# 01_Raspberry_Hat_7_Schematic.net
KiCad netlist of a schematic drawn in EAGLE
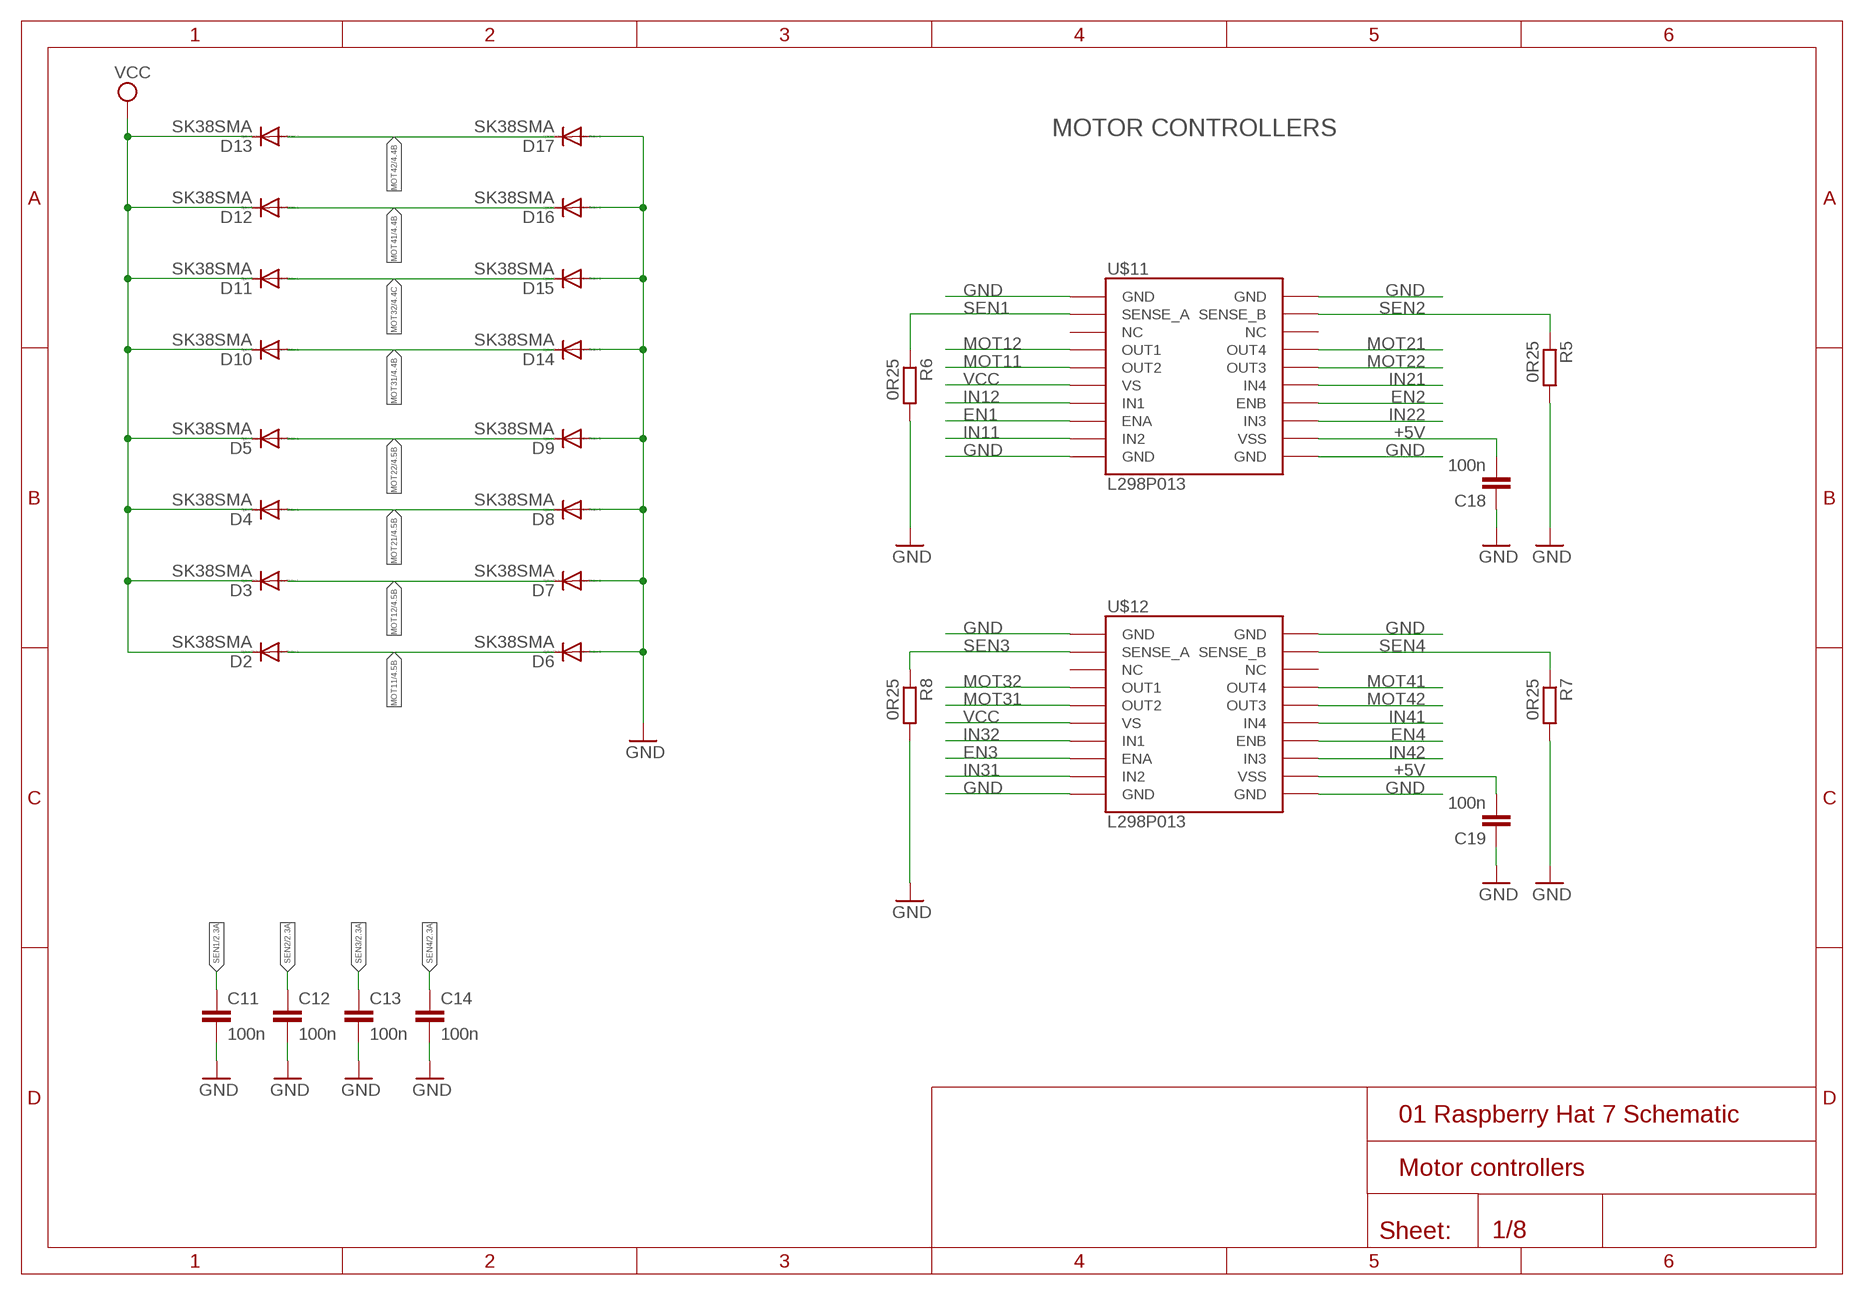
[diagram p0: schematic, sheet 1]
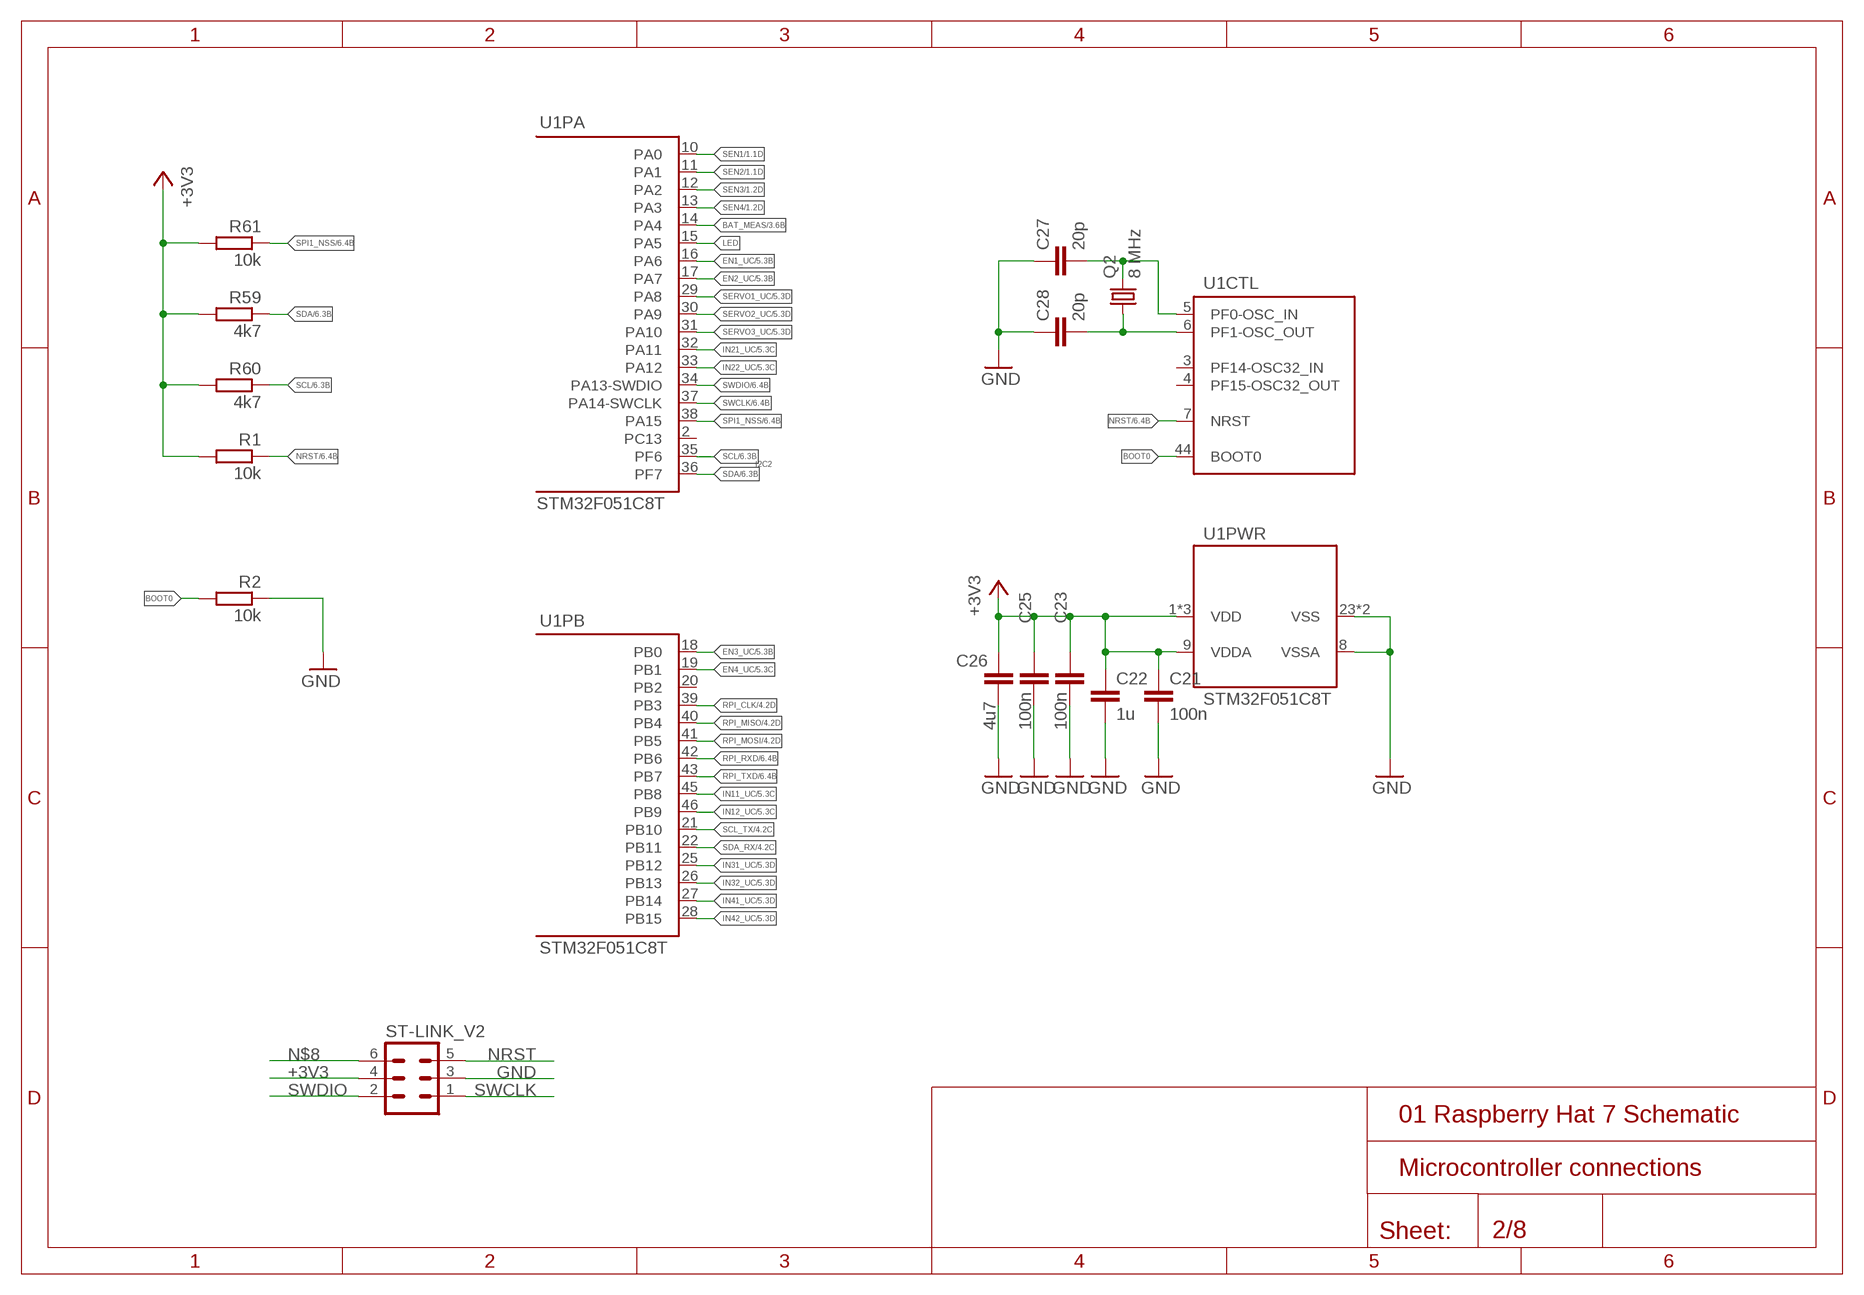
[diagram p1: schematic, sheet 2]
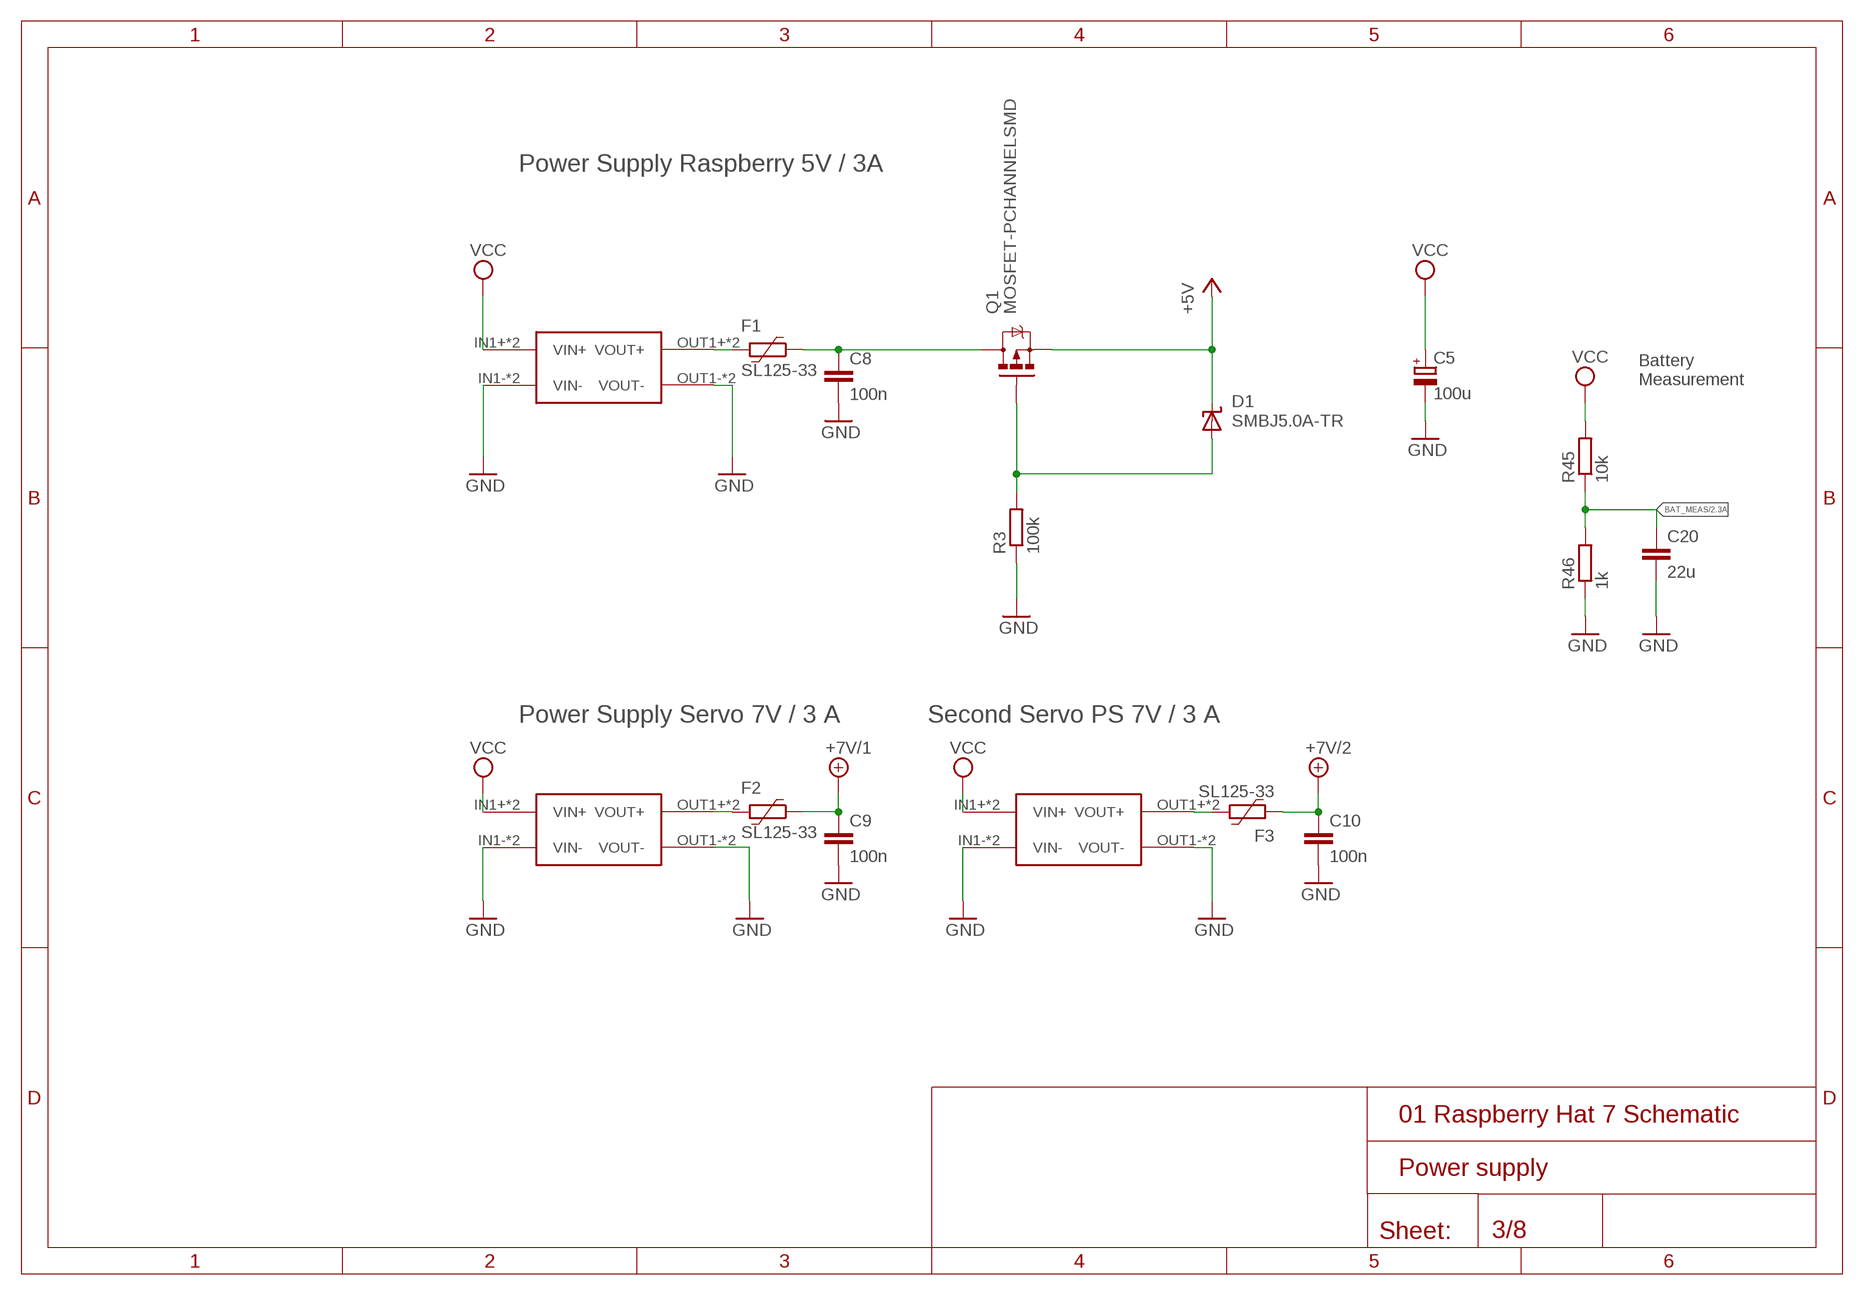
[diagram p2: schematic, sheet 3]
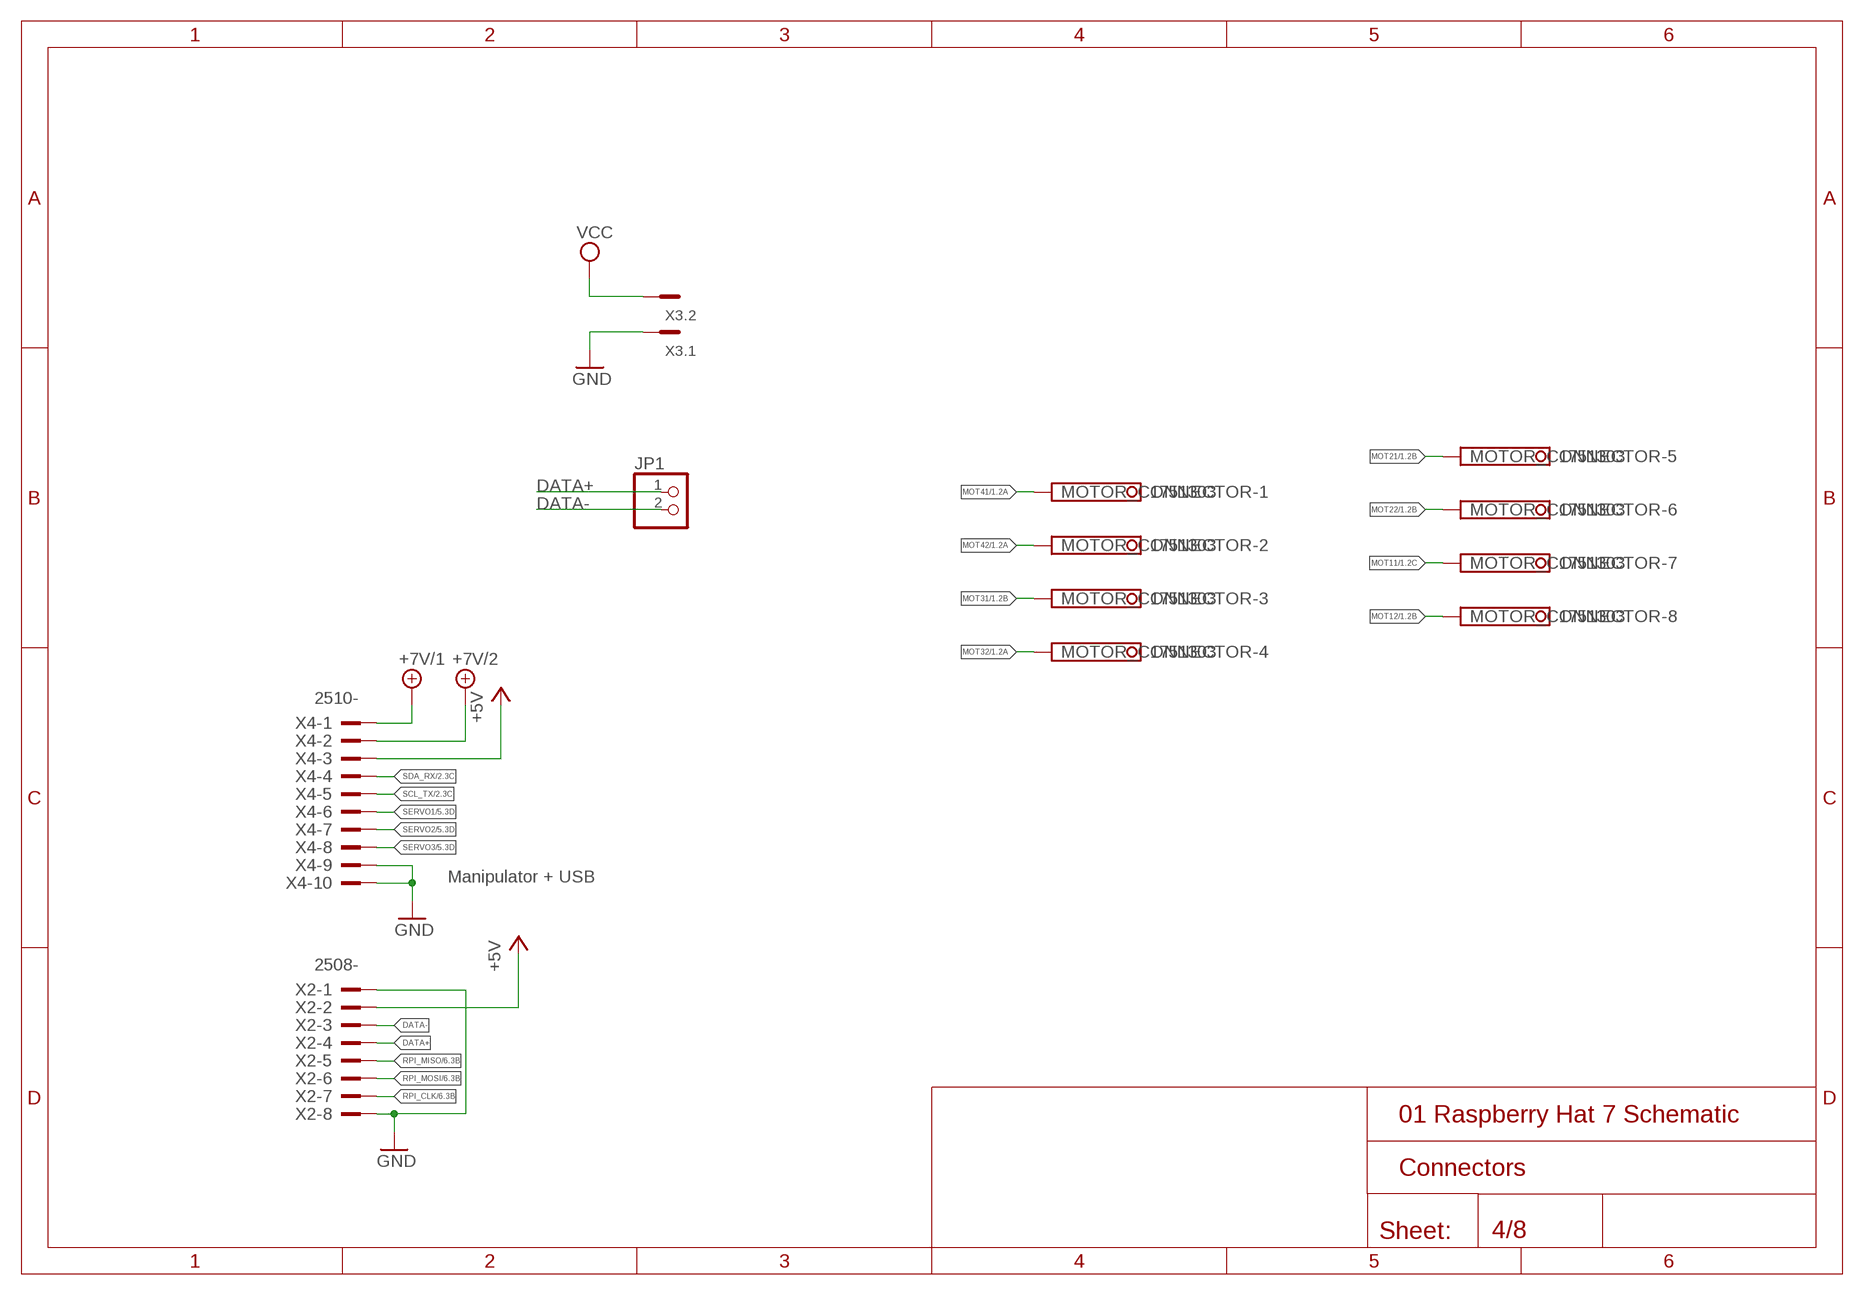
[diagram p3: schematic, sheet 4]
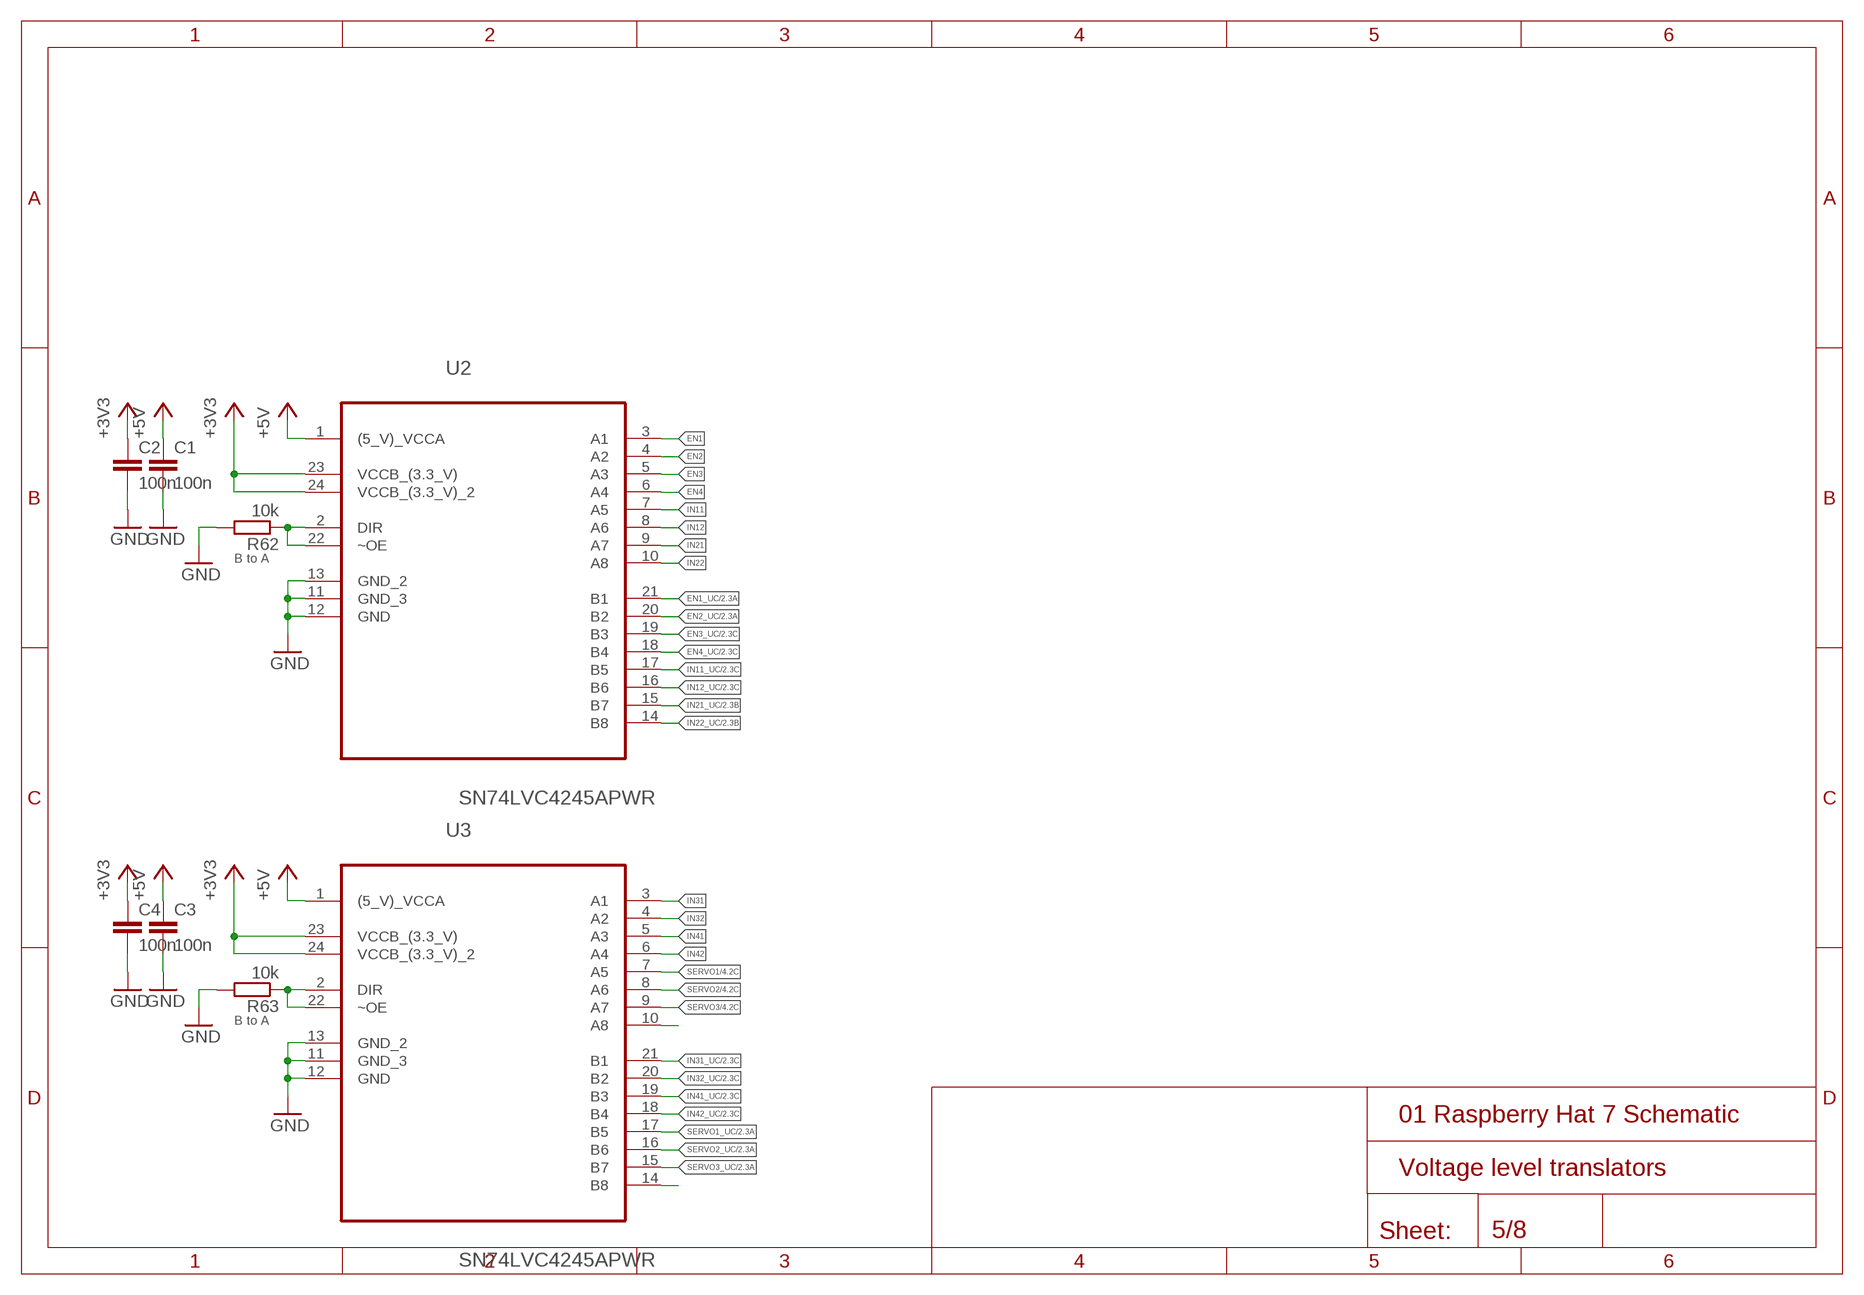
[diagram p4: schematic, sheet 5]
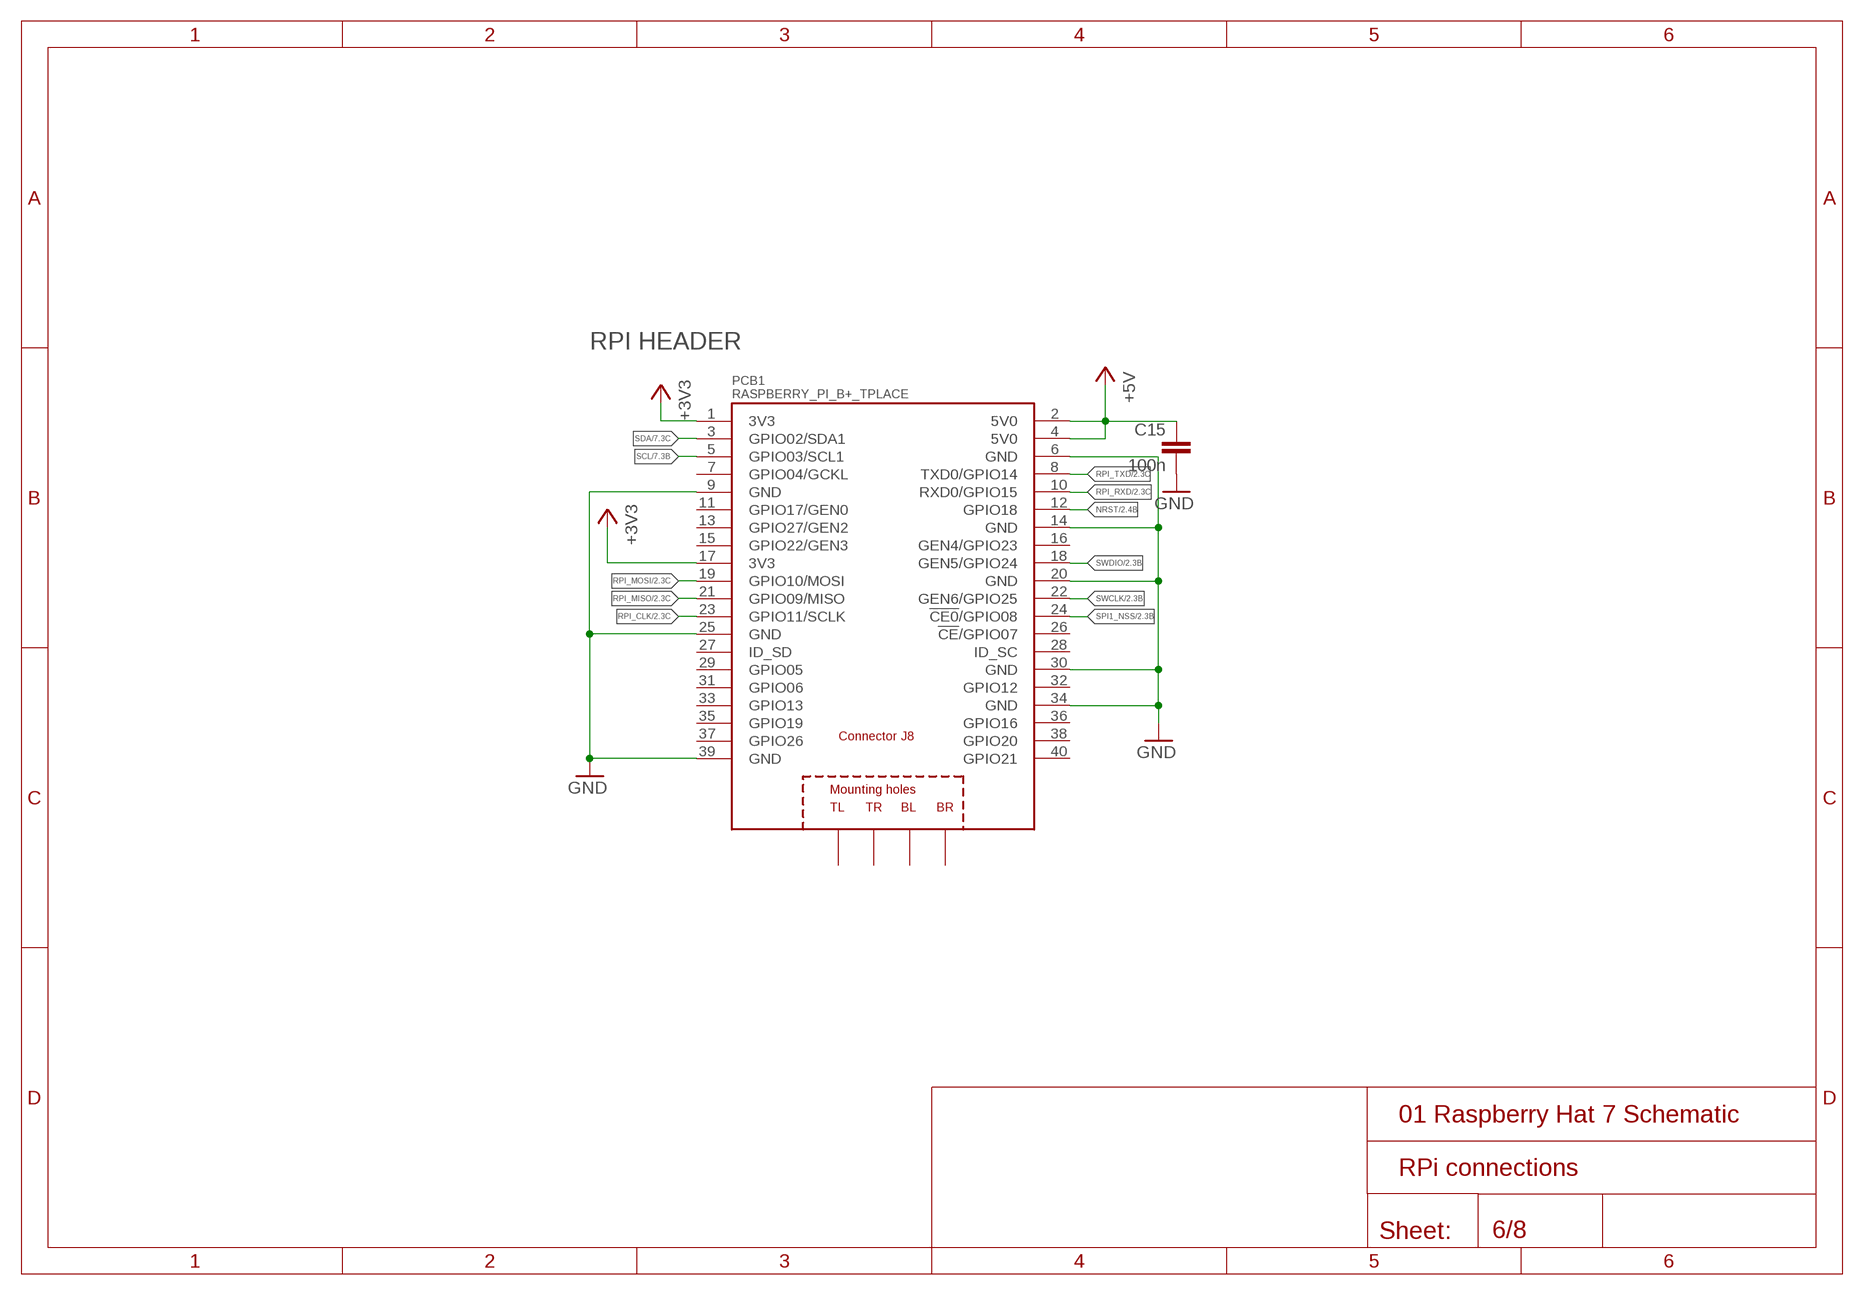
[diagram p5: schematic, sheet 6]
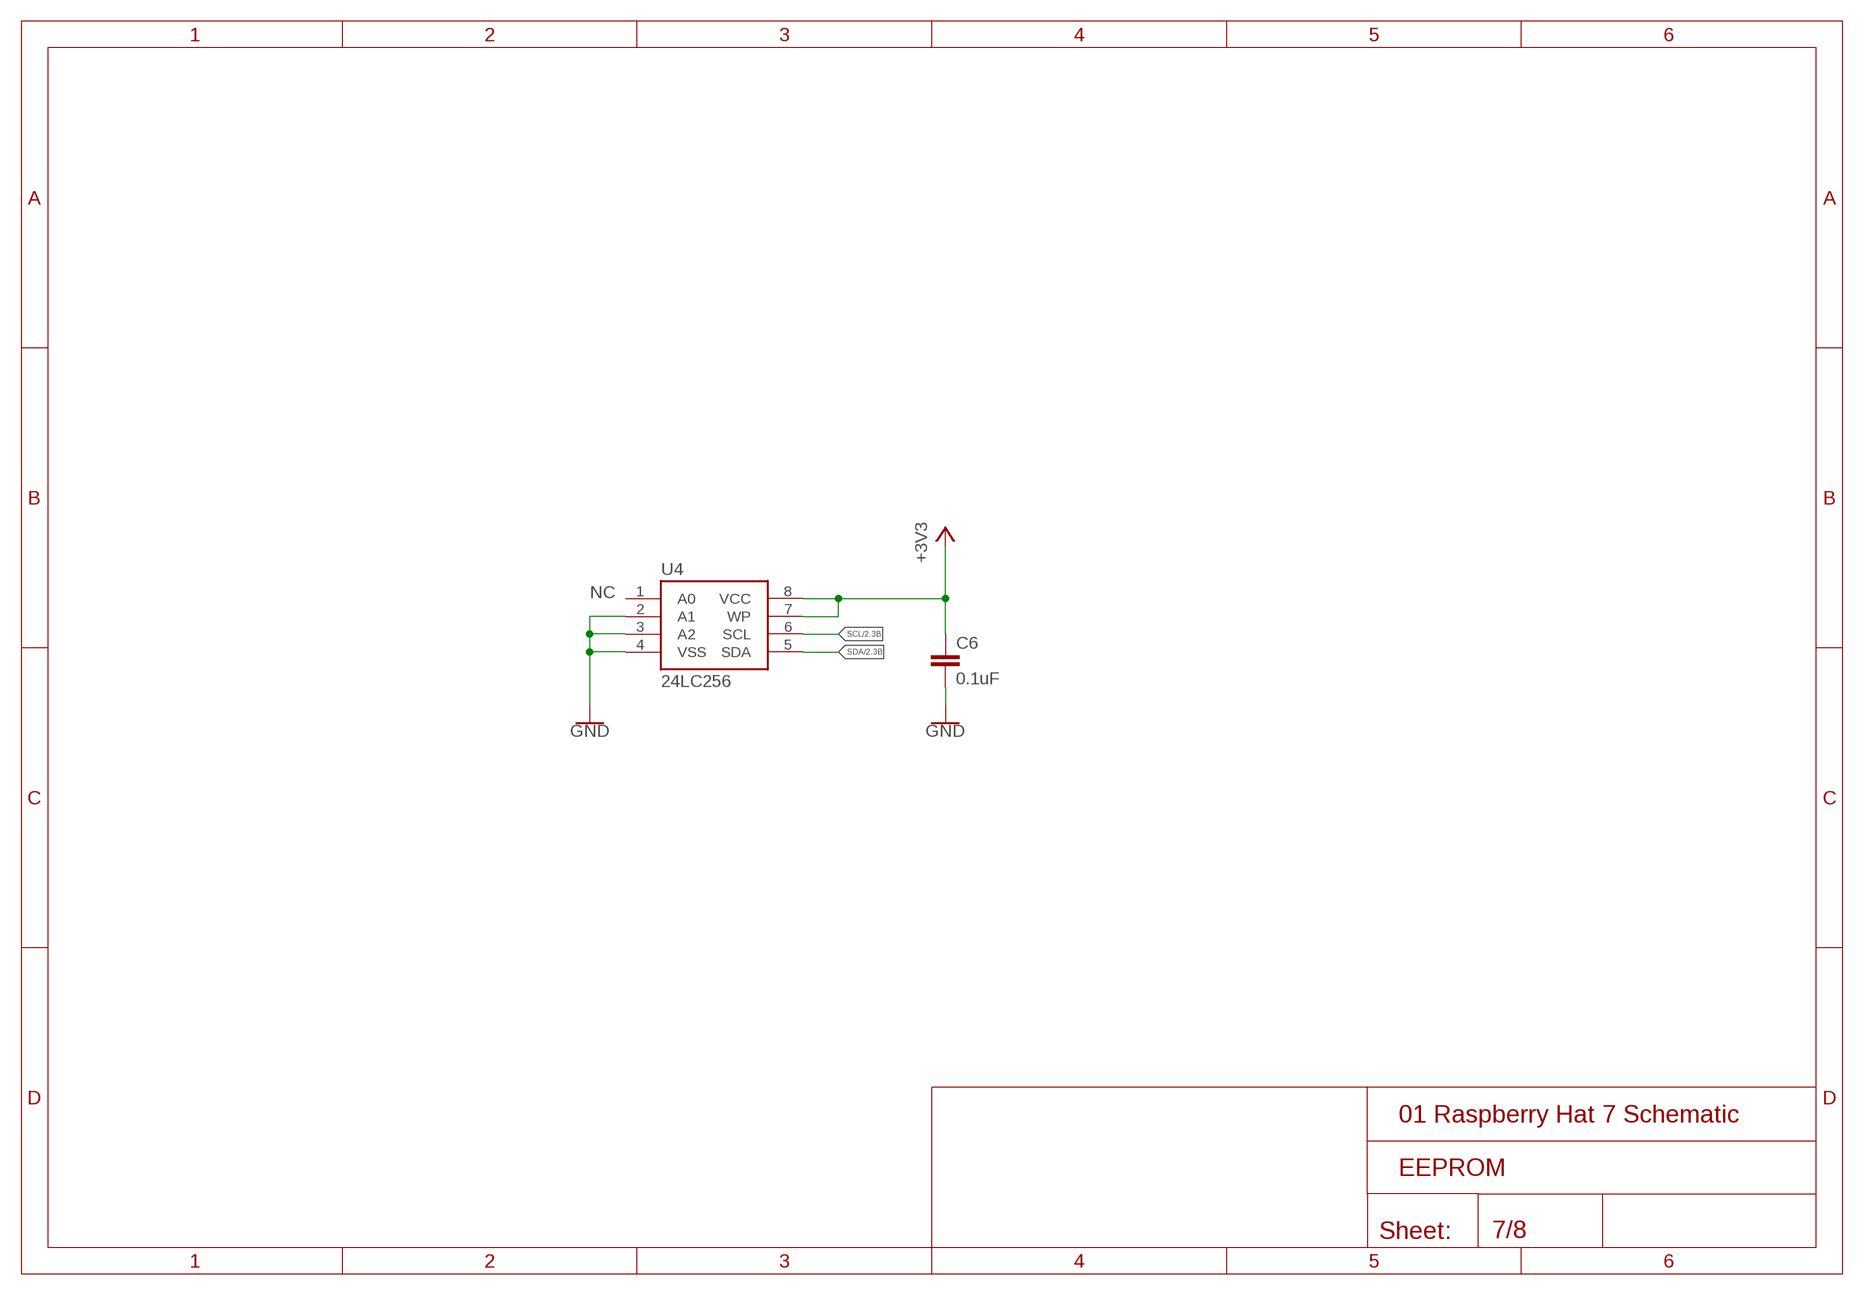
[diagram p6: schematic, sheet 7]
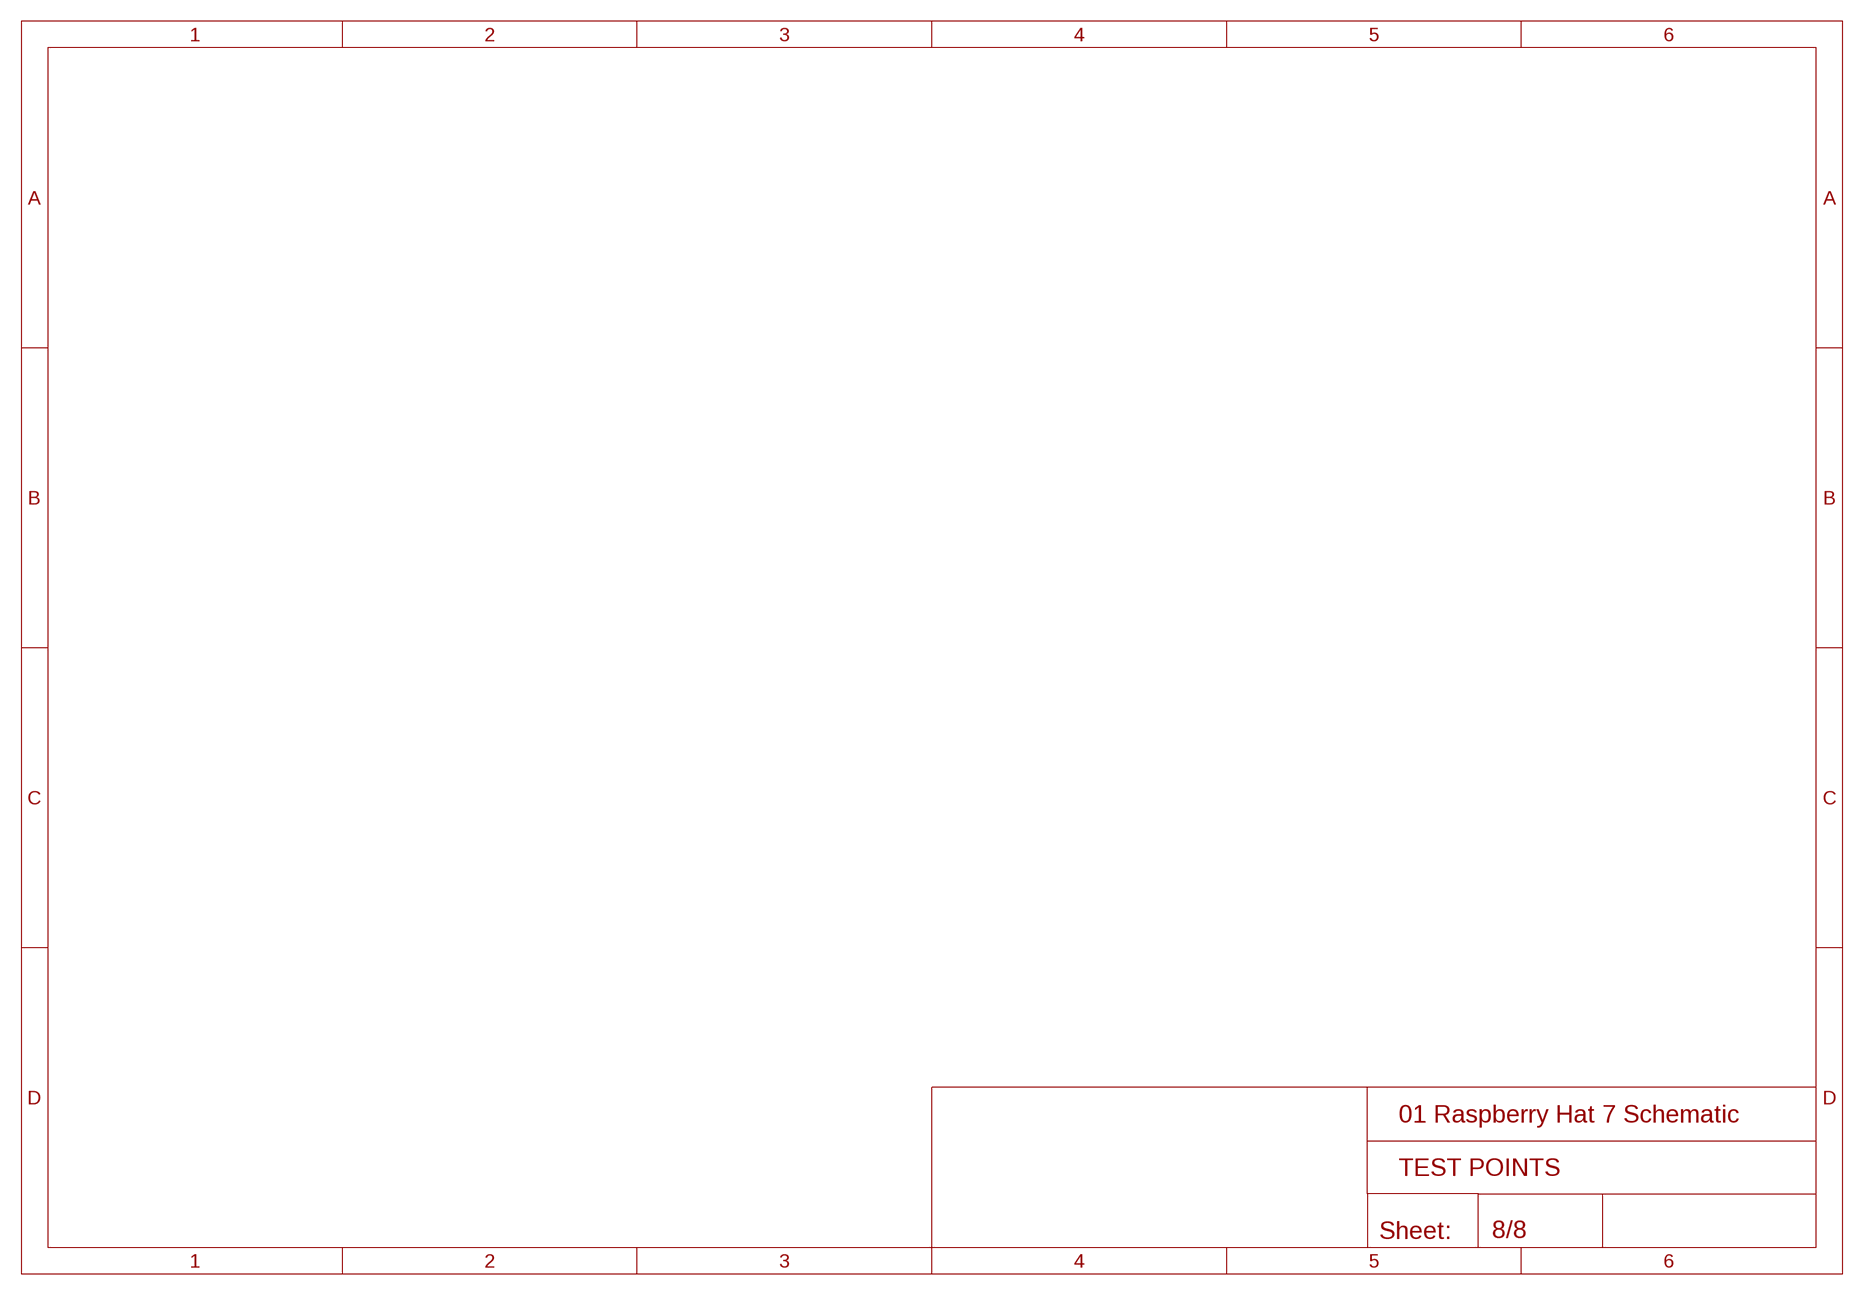
[diagram p7: schematic, sheet 8]

(export (version "E")
  (design (tool "Eeschema 10.0.6"))
  (components
    (comp (ref "C11")
      (value "100n")
      (footprint "eagle-import:C0603K")
      (libsource (lib "eagle-import") (part "resistor_348_C-EUC0603K"))
    )
    (comp (ref "C12")
      (value "100n")
      (footprint "eagle-import:C0603K")
      (libsource (lib "eagle-import") (part "resistor_348_C-EUC0603K"))
    )
    (comp (ref "C13")
      (value "100n")
      (footprint "eagle-import:C0603K")
      (libsource (lib "eagle-import") (part "resistor_348_C-EUC0603K"))
    )
    (comp (ref "C14")
      (value "100n")
      (footprint "eagle-import:C0603K")
      (libsource (lib "eagle-import") (part "resistor_348_C-EUC0603K"))
    )
    (comp (ref "C18")
      (value "100n")
      (footprint "eagle-import:C0603K")
      (libsource (lib "eagle-import") (part "resistor_348_C-EUC0603K"))
    )
    (comp (ref "C19")
      (value "100n")
      (footprint "eagle-import:C0603K")
      (libsource (lib "eagle-import") (part "resistor_348_C-EUC0603K"))
    )
    (comp (ref "D2")
      (value "SK38SMA")
      (footprint "eagle-import:SOD123")
      (libsource (lib "eagle-import") (part "DIODE-SOD123"))
    )
    (comp (ref "D3")
      (value "SK38SMA")
      (footprint "eagle-import:SOD123")
      (libsource (lib "eagle-import") (part "DIODE-SOD123"))
    )
    (comp (ref "D4")
      (value "SK38SMA")
      (footprint "eagle-import:SOD123")
      (libsource (lib "eagle-import") (part "DIODE-SOD123"))
    )
    (comp (ref "D5")
      (value "SK38SMA")
      (footprint "eagle-import:SOD123")
      (libsource (lib "eagle-import") (part "DIODE-SOD123"))
    )
    (comp (ref "D6")
      (value "SK38SMA")
      (footprint "eagle-import:SOD123")
      (libsource (lib "eagle-import") (part "DIODE-SOD123"))
    )
    (comp (ref "D7")
      (value "SK38SMA")
      (footprint "eagle-import:SOD123")
      (libsource (lib "eagle-import") (part "DIODE-SOD123"))
    )
    (comp (ref "D8")
      (value "SK38SMA")
      (footprint "eagle-import:SOD123")
      (libsource (lib "eagle-import") (part "DIODE-SOD123"))
    )
    (comp (ref "D9")
      (value "SK38SMA")
      (footprint "eagle-import:SOD123")
      (libsource (lib "eagle-import") (part "DIODE-SOD123"))
    )
    (comp (ref "D10")
      (value "SK38SMA")
      (footprint "eagle-import:SOD123")
      (libsource (lib "eagle-import") (part "DIODE-SOD123"))
    )
    (comp (ref "D11")
      (value "SK38SMA")
      (footprint "eagle-import:SOD123")
      (libsource (lib "eagle-import") (part "DIODE-SOD123"))
    )
    (comp (ref "D12")
      (value "SK38SMA")
      (footprint "eagle-import:SOD123")
      (libsource (lib "eagle-import") (part "DIODE-SOD123"))
    )
    (comp (ref "D13")
      (value "SK38SMA")
      (footprint "eagle-import:SOD123")
      (libsource (lib "eagle-import") (part "DIODE-SOD123"))
    )
    (comp (ref "D14")
      (value "SK38SMA")
      (footprint "eagle-import:SOD123")
      (libsource (lib "eagle-import") (part "DIODE-SOD123"))
    )
    (comp (ref "D15")
      (value "SK38SMA")
      (footprint "eagle-import:SOD123")
      (libsource (lib "eagle-import") (part "DIODE-SOD123"))
    )
    (comp (ref "D16")
      (value "SK38SMA")
      (footprint "eagle-import:SOD123")
      (libsource (lib "eagle-import") (part "DIODE-SOD123"))
    )
    (comp (ref "D17")
      (value "SK38SMA")
      (footprint "eagle-import:SOD123")
      (libsource (lib "eagle-import") (part "DIODE-SOD123"))
    )
    (comp (ref "R5")
      (value "0R25")
      (footprint "eagle-import:R2512")
      (libsource (lib "eagle-import") (part "R-EU_R2512"))
    )
    (comp (ref "R6")
      (value "0R25")
      (footprint "eagle-import:R2512")
      (libsource (lib "eagle-import") (part "R-EU_R2512"))
    )
    (comp (ref "R7")
      (value "0R25")
      (footprint "eagle-import:R2512")
      (libsource (lib "eagle-import") (part "R-EU_R2512"))
    )
    (comp (ref "R8")
      (value "0R25")
      (footprint "eagle-import:R2512")
      (libsource (lib "eagle-import") (part "R-EU_R2512"))
    )
    (comp (ref "U$11")
      (value "L298P013")
      (footprint "eagle-import:POWERSO20")
      (libsource (lib "eagle-import") (part "L298_BRIDGE_DRIVER"))
    )
    (comp (ref "U$12")
      (value "L298P013")
      (footprint "eagle-import:POWERSO20")
      (libsource (lib "eagle-import") (part "L298_BRIDGE_DRIVER"))
    )
    (comp (ref "C1")
      (value "100n")
      (footprint "eagle-import:C0603K")
      (libsource (lib "eagle-import") (part "resistor_348_C-EUC0603K"))
    )
    (comp (ref "C2")
      (value "100n")
      (footprint "eagle-import:C0603K")
      (libsource (lib "eagle-import") (part "resistor_348_C-EUC0603K"))
    )
    (comp (ref "C3")
      (value "100n")
      (footprint "eagle-import:C0603K")
      (libsource (lib "eagle-import") (part "resistor_348_C-EUC0603K"))
    )
    (comp (ref "C4")
      (value "100n")
      (footprint "eagle-import:C0603K")
      (libsource (lib "eagle-import") (part "resistor_348_C-EUC0603K"))
    )
    (comp (ref "R62")
      (value "10k")
      (footprint "eagle-import:R0603")
      (libsource (lib "eagle-import") (part "resistor_348_R-EU_R0603"))
    )
    (comp (ref "R63")
      (value "10k")
      (footprint "eagle-import:R0603")
      (libsource (lib "eagle-import") (part "resistor_348_R-EU_R0603"))
    )
    (comp (ref "U2")
      (value "SN74LVC4245APWR")
      (footprint "eagle-import:SOP65P640X120-24N")
      (libsource (lib "eagle-import") (part "SN74LVC4245APWR"))
    )
    (comp (ref "U3")
      (value "SN74LVC4245APWR")
      (footprint "eagle-import:SOP65P640X120-24N")
      (libsource (lib "eagle-import") (part "SN74LVC4245APWR"))
    )
    (comp (ref "C21")
      (value "100n")
      (footprint "eagle-import:C0603K")
      (libsource (lib "eagle-import") (part "resistor_348_C-EUC0603K"))
    )
    (comp (ref "C22")
      (value "1u")
      (footprint "eagle-import:C0603K")
      (libsource (lib "eagle-import") (part "resistor_348_C-EUC0603K"))
    )
    (comp (ref "C23")
      (value "100n")
      (footprint "eagle-import:C0603K")
      (libsource (lib "eagle-import") (part "resistor_348_C-EUC0603K"))
    )
    (comp (ref "C25")
      (value "100n")
      (footprint "eagle-import:C0603K")
      (libsource (lib "eagle-import") (part "resistor_348_C-EUC0603K"))
    )
    (comp (ref "C26")
      (value "4u7")
      (footprint "eagle-import:C0603K")
      (libsource (lib "eagle-import") (part "resistor_348_C-EUC0603K"))
    )
    (comp (ref "C27")
      (value "20p")
      (footprint "eagle-import:C0603K")
      (libsource (lib "eagle-import") (part "resistor_348_C-EUC0603K"))
    )
    (comp (ref "C28")
      (value "20p")
      (footprint "eagle-import:C0603K")
      (libsource (lib "eagle-import") (part "resistor_348_C-EUC0603K"))
    )
    (comp (ref "Q2")
      (value "8 MHz")
      (footprint "eagle-import:HC49UP")
      (libsource (lib "eagle-import") (part "CRYSTALHC49UP"))
    )
    (comp (ref "R1")
      (value "10k")
      (footprint "eagle-import:R0603")
      (libsource (lib "eagle-import") (part "resistor_348_R-EU_R0603"))
    )
    (comp (ref "R2")
      (value "10k")
      (footprint "eagle-import:R0603")
      (libsource (lib "eagle-import") (part "resistor_348_R-EU_R0603"))
    )
    (comp (ref "R59")
      (value "4k7")
      (footprint "eagle-import:R0603")
      (libsource (lib "eagle-import") (part "resistor_348_R-EU_R0603"))
    )
    (comp (ref "R60")
      (value "4k7")
      (footprint "eagle-import:R0603")
      (libsource (lib "eagle-import") (part "resistor_348_R-EU_R0603"))
    )
    (comp (ref "R61")
      (value "10k")
      (footprint "eagle-import:R0603")
      (libsource (lib "eagle-import") (part "resistor_348_R-EU_R0603"))
    )
    (comp (ref "ST-LINK_V2")
      (value "ML6")
      (footprint "eagle-import:ML6")
      (libsource (lib "eagle-import") (part "ML6"))
    )
    (comp (ref "U1")
      (value "STM32F051C8T")
      (footprint "eagle-import:LQFP48")
      (libsource (lib "eagle-import") (part "STM32F051CT8"))
    )
    (comp (ref "C15")
      (value "100n")
      (footprint "eagle-import:C0603K")
      (libsource (lib "eagle-import") (part "resistor_348_C-EUC0603K"))
    )
    (comp (ref "PCB1")
      (value "RASPBERRY_PI_B+_TPLACE")
      (footprint "eagle-import:RASPBERRY_PI_BPLUS_TPLACE")
      (libsource (lib "eagle-import") (part "RASPBERRY_PI_B+_TPLACE"))
    )
    (comp (ref "JP1")
      (value "PINHD-1X2")
      (footprint "eagle-import:1X02")
      (libsource (lib "eagle-import") (part "PINHD-1X2"))
    )
    (comp (ref "MOTOR_CONNECTOR")
      (value "1751303")
      (footprint "eagle-import:1751303")
      (libsource (lib "eagle-import") (part "1751303"))
    )
    (comp (ref "X2")
      (value "2508-")
      (footprint "eagle-import:PAK100_2500-10")
      (fields (field (name "MF") "3M") (field (name "MPN") "2510-6002UB"))
      (libsource (lib "eagle-import") (part "2508-"))
    )
    (comp (ref "X3")
      (value "MC2")
      (footprint "eagle-import:MC2")
      (libsource (lib "eagle-import") (part "MC2"))
    )
    (comp (ref "X4")
      (value "2510-")
      (footprint "eagle-import:PAK100_2500-10")
      (fields (field (name "MF") "3M") (field (name "MPN") "2510-6002UB"))
      (libsource (lib "eagle-import") (part "2510-"))
    )
    (comp (ref "C5")
      (value "100u")
      (footprint "eagle-import:153CLV-0807")
      (libsource (lib "eagle-import") (part "CPOL-EU153CLV-0807"))
    )
    (comp (ref "C8")
      (value "100n")
      (footprint "eagle-import:C0603K")
      (libsource (lib "eagle-import") (part "resistor_348_C-EUC0603K"))
    )
    (comp (ref "C9")
      (value "100n")
      (footprint "eagle-import:C0603K")
      (libsource (lib "eagle-import") (part "resistor_348_C-EUC0603K"))
    )
    (comp (ref "C10")
      (value "100n")
      (footprint "eagle-import:C0603K")
      (libsource (lib "eagle-import") (part "resistor_348_C-EUC0603K"))
    )
    (comp (ref "C20")
      (value "22u")
      (footprint "eagle-import:C0603K")
      (libsource (lib "eagle-import") (part "resistor_348_C-EUC0603K"))
    )
    (comp (ref "D1")
      (value "SMBJ5.0A-TR")
      (footprint "eagle-import:SMBJ")
      (libsource (lib "eagle-import") (part "SUPPRESSOR-SMBJ"))
    )
    (comp (ref "F1")
      (value "SL125-33")
      (footprint "eagle-import:2920L")
      (fields (field (name "MF") "Littelfuse") (field (name "MPN") "2920L050"))
      (libsource (lib "eagle-import") (part "?2920L050"))
    )
    (comp (ref "F2")
      (value "SL125-33")
      (footprint "eagle-import:2920L")
      (fields (field (name "MF") "Littelfuse") (field (name "MPN") "2920L050"))
      (libsource (lib "eagle-import") (part "?2920L050"))
    )
    (comp (ref "F3")
      (value "SL125-33")
      (footprint "eagle-import:2920L")
      (fields (field (name "MF") "Littelfuse") (field (name "MPN") "2920L050"))
      (libsource (lib "eagle-import") (part "?2920L050"))
    )
    (comp (ref "Q1")
      (value "MOSFET-PCHANNELSMD")
      (footprint "eagle-import:SOT23-3")
      (libsource (lib "eagle-import") (part "MOSFET-PCHANNELSMD"))
    )
    (comp (ref "R3")
      (value "100k")
      (footprint "eagle-import:R0603")
      (libsource (lib "eagle-import") (part "R-EU_R0603"))
    )
    (comp (ref "R45")
      (value "10k")
      (footprint "eagle-import:R0603")
      (libsource (lib "eagle-import") (part "resistor_348_R-EU_R0603"))
    )
    (comp (ref "R46")
      (value "1k")
      (footprint "eagle-import:R0603")
      (libsource (lib "eagle-import") (part "resistor_348_R-EU_R0603"))
    )
    (comp (ref "U$1")
      (value "MP1584")
      (footprint "eagle-import:DC-BRICK")
      (libsource (lib "eagle-import") (part "MP1584"))
    )
    (comp (ref "U$2")
      (value "MP1584")
      (footprint "eagle-import:DC-BRICK")
      (libsource (lib "eagle-import") (part "MP1584"))
    )
    (comp (ref "U$3")
      (value "MP1584")
      (footprint "eagle-import:DC-BRICK")
      (libsource (lib "eagle-import") (part "MP1584"))
    )
    (comp (ref "C6")
      (value "0.1uF")
      (footprint "eagle-import:C0603")
      (libsource (lib "eagle-import") (part "C-EUC0603"))
    )
    (comp (ref "U4")
      (value "24LC256")
      (footprint "eagle-import:SO08")
      (libsource (lib "eagle-import") (part "EEPROM-I2CSMD"))
    )
  )
  (nets
    (net (code "1") (name "+3V3") (class "Default")
      (node (ref "C2") (pin "1") (pinfunction "1_1") (pintype "passive"))
      (node (ref "C21") (pin "1") (pinfunction "1_1") (pintype "passive"))
      (node (ref "C22") (pin "1") (pinfunction "1_1") (pintype "passive"))
      (node (ref "C23") (pin "1") (pinfunction "1_1") (pintype "passive"))
      (node (ref "C25") (pin "1") (pinfunction "1_1") (pintype "passive"))
      (node (ref "C26") (pin "1") (pinfunction "1_1") (pintype "passive"))
      (node (ref "C4") (pin "1") (pinfunction "1_1") (pintype "passive"))
      (node (ref "C6") (pin "1") (pinfunction "1_1") (pintype "passive"))
      (node (ref "PCB1") (pin "1") (pinfunction "3V3_1") (pintype "power_in"))
      (node (ref "PCB1") (pin "17") (pinfunction "3V3_17") (pintype "power_in"))
      (node (ref "R1") (pin "2") (pinfunction "2_2") (pintype "passive"))
      (node (ref "R59") (pin "2") (pinfunction "2_2") (pintype "passive"))
      (node (ref "R60") (pin "2") (pinfunction "2_2") (pintype "passive"))
      (node (ref "R61") (pin "2") (pinfunction "2_2") (pintype "passive"))
      (node (ref "ST-LINK_V2") (pin "4") (pinfunction "4_4") (pintype "passive"))
      (node (ref "U1") (pin "1") (pinfunction "VDD_1") (pintype "power_in"))
      (node (ref "U1") (pin "24") (pinfunction "VDD_24") (pintype "power_in"))
      (node (ref "U1") (pin "48") (pinfunction "VDD_48") (pintype "power_in"))
      (node (ref "U1") (pin "9") (pinfunction "VDDA_9") (pintype "power_in"))
      (node (ref "U2") (pin "23") (pinfunction "VCCB_(3.3_V)_23") (pintype "power_in"))
      (node (ref "U2") (pin "24") (pinfunction "VCCB_(3.3_V)_2_24") (pintype "power_in"))
      (node (ref "U3") (pin "23") (pinfunction "VCCB_(3.3_V)_23") (pintype "power_in"))
      (node (ref "U3") (pin "24") (pinfunction "VCCB_(3.3_V)_2_24") (pintype "power_in"))
      (node (ref "U4") (pin "7") (pinfunction "WP_7") (pintype "bidirectional"))
      (node (ref "U4") (pin "8") (pinfunction "VCC_8") (pintype "power_in"))
    )
    (net (code "2") (name "+5V") (class "Default")
      (node (ref "C1") (pin "1") (pinfunction "1_1") (pintype "passive"))
      (node (ref "C15") (pin "1") (pinfunction "1_1") (pintype "passive"))
      (node (ref "C18") (pin "2") (pinfunction "2_2") (pintype "passive"))
      (node (ref "C19") (pin "2") (pinfunction "2_2") (pintype "passive"))
      (node (ref "C3") (pin "1") (pinfunction "1_1") (pintype "passive"))
      (node (ref "D1") (pin "C") (pinfunction "C_C") (pintype "passive"))
      (node (ref "PCB1") (pin "2") (pinfunction "5V0_2") (pintype "power_in"))
      (node (ref "PCB1") (pin "4") (pinfunction "5V0_4") (pintype "power_in"))
      (node (ref "Q1") (pin "2") (pinfunction "S_2") (pintype "passive"))
      (node (ref "U$11") (pin "12") (pinfunction "VSS_12") (pintype "bidirectional"))
      (node (ref "U$12") (pin "12") (pinfunction "VSS_12") (pintype "bidirectional"))
      (node (ref "U2") (pin "1") (pinfunction "(5_V)_VCCA_1") (pintype "power_in"))
      (node (ref "U3") (pin "1") (pinfunction "(5_V)_VCCA_1") (pintype "power_in"))
      (node (ref "X2") (pin "2") (pinfunction "KL_2") (pintype "passive"))
      (node (ref "X4") (pin "3") (pinfunction "KL_3") (pintype "passive"))
    )
    (net (code "3") (name "+7V{slash}1") (class "Default")
      (node (ref "C9") (pin "1") (pinfunction "1_1") (pintype "passive"))
      (node (ref "F2") (pin "1") (pinfunction "1_1") (pintype "passive"))
      (node (ref "X4") (pin "1") (pinfunction "KL_1") (pintype "passive"))
    )
    (net (code "4") (name "+7V{slash}2") (class "Default")
      (node (ref "C10") (pin "1") (pinfunction "1_1") (pintype "passive"))
      (node (ref "F3") (pin "2") (pinfunction "2_2") (pintype "passive"))
      (node (ref "X4") (pin "2") (pinfunction "KL_2") (pintype "passive"))
    )
    (net (code "5") (name "BAT_MEAS") (class "Default")
      (node (ref "C20") (pin "1") (pinfunction "1_1") (pintype "passive"))
      (node (ref "R45") (pin "1") (pinfunction "1_1") (pintype "passive"))
      (node (ref "R46") (pin "2") (pinfunction "2_2") (pintype "passive"))
      (node (ref "U1") (pin "14") (pinfunction "PA4_14") (pintype "bidirectional"))
    )
    (net (code "6") (name "BOOT0") (class "Default")
      (node (ref "R2") (pin "2") (pinfunction "2_2") (pintype "passive"))
      (node (ref "U1") (pin "44") (pinfunction "BOOT0_44") (pintype "bidirectional"))
    )
    (net (code "7") (name "DATA+") (class "Default")
      (node (ref "JP1") (pin "1") (pinfunction "1_1") (pintype "passive"))
      (node (ref "X2") (pin "4") (pinfunction "KL_4") (pintype "passive"))
    )
    (net (code "8") (name "DATA-") (class "Default")
      (node (ref "JP1") (pin "2") (pinfunction "2_2") (pintype "passive"))
      (node (ref "X2") (pin "3") (pinfunction "KL_3") (pintype "passive"))
    )
    (net (code "9") (name "EN1") (class "Default")
      (node (ref "U$11") (pin "8") (pinfunction "ENA_8") (pintype "bidirectional"))
      (node (ref "U2") (pin "3") (pinfunction "A1_3") (pintype "output"))
    )
    (net (code "10") (name "EN1_UC") (class "Default")
      (node (ref "U1") (pin "16") (pinfunction "PA6_16") (pintype "bidirectional"))
      (node (ref "U2") (pin "21") (pinfunction "B1_21") (pintype "output"))
    )
    (net (code "11") (name "EN2") (class "Default")
      (node (ref "U$11") (pin "14") (pinfunction "ENB_14") (pintype "bidirectional"))
      (node (ref "U2") (pin "4") (pinfunction "A2_4") (pintype "output"))
    )
    (net (code "12") (name "EN2_UC") (class "Default")
      (node (ref "U1") (pin "17") (pinfunction "PA7_17") (pintype "bidirectional"))
      (node (ref "U2") (pin "20") (pinfunction "B2_20") (pintype "output"))
    )
    (net (code "13") (name "EN3") (class "Default")
      (node (ref "U$12") (pin "8") (pinfunction "ENA_8") (pintype "bidirectional"))
      (node (ref "U2") (pin "5") (pinfunction "A3_5") (pintype "output"))
    )
    (net (code "14") (name "EN3_UC") (class "Default")
      (node (ref "U1") (pin "18") (pinfunction "PB0_18") (pintype "bidirectional"))
      (node (ref "U2") (pin "19") (pinfunction "B3_19") (pintype "output"))
    )
    (net (code "15") (name "EN4") (class "Default")
      (node (ref "U$12") (pin "14") (pinfunction "ENB_14") (pintype "bidirectional"))
      (node (ref "U2") (pin "6") (pinfunction "A4_6") (pintype "output"))
    )
    (net (code "16") (name "EN4_UC") (class "Default")
      (node (ref "U1") (pin "19") (pinfunction "PB1_19") (pintype "bidirectional"))
      (node (ref "U2") (pin "18") (pinfunction "B4_18") (pintype "output"))
    )
    (net (code "17") (name "GND") (class "Default")
      (node (ref "C1") (pin "2") (pinfunction "2_2") (pintype "passive"))
      (node (ref "C10") (pin "2") (pinfunction "2_2") (pintype "passive"))
      (node (ref "C11") (pin "2") (pinfunction "2_2") (pintype "passive"))
      (node (ref "C12") (pin "2") (pinfunction "2_2") (pintype "passive"))
      (node (ref "C13") (pin "2") (pinfunction "2_2") (pintype "passive"))
      (node (ref "C14") (pin "2") (pinfunction "2_2") (pintype "passive"))
      (node (ref "C15") (pin "2") (pinfunction "2_2") (pintype "passive"))
      (node (ref "C18") (pin "1") (pinfunction "1_1") (pintype "passive"))
      (node (ref "C19") (pin "1") (pinfunction "1_1") (pintype "passive"))
      (node (ref "C2") (pin "2") (pinfunction "2_2") (pintype "passive"))
      (node (ref "C20") (pin "2") (pinfunction "2_2") (pintype "passive"))
      (node (ref "C21") (pin "2") (pinfunction "2_2") (pintype "passive"))
      (node (ref "C22") (pin "2") (pinfunction "2_2") (pintype "passive"))
      (node (ref "C23") (pin "2") (pinfunction "2_2") (pintype "passive"))
      (node (ref "C25") (pin "2") (pinfunction "2_2") (pintype "passive"))
      (node (ref "C26") (pin "2") (pinfunction "2_2") (pintype "passive"))
      (node (ref "C27") (pin "1") (pinfunction "1_1") (pintype "passive"))
      (node (ref "C28") (pin "1") (pinfunction "1_1") (pintype "passive"))
      (node (ref "C3") (pin "2") (pinfunction "2_2") (pintype "passive"))
      (node (ref "C4") (pin "2") (pinfunction "2_2") (pintype "passive"))
      (node (ref "C5") (pin "-") (pinfunction "-_-") (pintype "passive"))
      (node (ref "C6") (pin "2") (pinfunction "2_2") (pintype "passive"))
      (node (ref "C8") (pin "2") (pinfunction "2_2") (pintype "passive"))
      (node (ref "C9") (pin "2") (pinfunction "2_2") (pintype "passive"))
      (node (ref "D14") (pin "A") (pinfunction "A_A") (pintype "passive"))
      (node (ref "D15") (pin "A") (pinfunction "A_A") (pintype "passive"))
      (node (ref "D16") (pin "A") (pinfunction "A_A") (pintype "passive"))
      (node (ref "D17") (pin "A") (pinfunction "A_A") (pintype "passive"))
      (node (ref "D6") (pin "A") (pinfunction "A_A") (pintype "passive"))
      (node (ref "D7") (pin "A") (pinfunction "A_A") (pintype "passive"))
      (node (ref "D8") (pin "A") (pinfunction "A_A") (pintype "passive"))
      (node (ref "D9") (pin "A") (pinfunction "A_A") (pintype "passive"))
      (node (ref "PCB1") (pin "14") (pinfunction "GND_14") (pintype "power_in"))
      (node (ref "PCB1") (pin "20") (pinfunction "GND_20") (pintype "power_in"))
      (node (ref "PCB1") (pin "25") (pinfunction "GND_25") (pintype "power_in"))
      (node (ref "PCB1") (pin "30") (pinfunction "GND_30") (pintype "power_in"))
      (node (ref "PCB1") (pin "34") (pinfunction "GND_34") (pintype "power_in"))
      (node (ref "PCB1") (pin "39") (pinfunction "GND_39") (pintype "power_in"))
      (node (ref "PCB1") (pin "6") (pinfunction "GND_6") (pintype "power_in"))
      (node (ref "PCB1") (pin "9") (pinfunction "GND_9") (pintype "power_in"))
      (node (ref "R2") (pin "1") (pinfunction "1_1") (pintype "passive"))
      (node (ref "R3") (pin "1") (pinfunction "1_1") (pintype "passive"))
      (node (ref "R46") (pin "1") (pinfunction "1_1") (pintype "passive"))
      (node (ref "R5") (pin "2") (pinfunction "2_2") (pintype "passive"))
      (node (ref "R6") (pin "2") (pinfunction "2_2") (pintype "passive"))
      (node (ref "R62") (pin "2") (pinfunction "2_2") (pintype "passive"))
      (node (ref "R63") (pin "2") (pinfunction "2_2") (pintype "passive"))
      (node (ref "R7") (pin "2") (pinfunction "2_2") (pintype "passive"))
      (node (ref "R8") (pin "2") (pinfunction "2_2") (pintype "passive"))
      (node (ref "ST-LINK_V2") (pin "3") (pinfunction "3_3") (pintype "passive"))
      (node (ref "U$1") (pin "IN1-") (pinfunction "VIN-_IN1-") (pintype "input"))
      (node (ref "U$1") (pin "IN2-") (pinfunction "VIN-_IN2-") (pintype "input"))
      (node (ref "U$1") (pin "OUT1-") (pinfunction "VOUT-_OUT1-") (pintype "output"))
      (node (ref "U$1") (pin "OUT2-") (pinfunction "VOUT-_OUT2-") (pintype "output"))
      (node (ref "U$11") (pin "1") (pinfunction "GND_1") (pintype "bidirectional"))
      (node (ref "U$11") (pin "10") (pinfunction "GND_10") (pintype "bidirectional"))
      (node (ref "U$11") (pin "11") (pinfunction "GND_11") (pintype "bidirectional"))
      (node (ref "U$11") (pin "20") (pinfunction "GND_20") (pintype "bidirectional"))
      (node (ref "U$12") (pin "1") (pinfunction "GND_1") (pintype "bidirectional"))
      (node (ref "U$12") (pin "10") (pinfunction "GND_10") (pintype "bidirectional"))
      (node (ref "U$12") (pin "11") (pinfunction "GND_11") (pintype "bidirectional"))
      (node (ref "U$12") (pin "20") (pinfunction "GND_20") (pintype "bidirectional"))
      (node (ref "U$2") (pin "IN1-") (pinfunction "VIN-_IN1-") (pintype "input"))
      (node (ref "U$2") (pin "IN2-") (pinfunction "VIN-_IN2-") (pintype "input"))
      (node (ref "U$2") (pin "OUT1-") (pinfunction "VOUT-_OUT1-") (pintype "output"))
      (node (ref "U$2") (pin "OUT2-") (pinfunction "VOUT-_OUT2-") (pintype "output"))
      (node (ref "U$3") (pin "IN1-") (pinfunction "VIN-_IN1-") (pintype "input"))
      (node (ref "U$3") (pin "IN2-") (pinfunction "VIN-_IN2-") (pintype "input"))
      (node (ref "U$3") (pin "OUT1-") (pinfunction "VOUT-_OUT1-") (pintype "output"))
      (node (ref "U$3") (pin "OUT2-") (pinfunction "VOUT-_OUT2-") (pintype "output"))
      (node (ref "U1") (pin "23") (pinfunction "VSS_23") (pintype "power_in"))
      (node (ref "U1") (pin "47") (pinfunction "VSS_47") (pintype "power_in"))
      (node (ref "U1") (pin "8") (pinfunction "VSSA_8") (pintype "power_in"))
      (node (ref "U2") (pin "11") (pinfunction "GND_3_11") (pintype "passive"))
      (node (ref "U2") (pin "12") (pinfunction "GND_12") (pintype "passive"))
      (node (ref "U2") (pin "13") (pinfunction "GND_2_13") (pintype "passive"))
      (node (ref "U3") (pin "11") (pinfunction "GND_3_11") (pintype "passive"))
      (node (ref "U3") (pin "12") (pinfunction "GND_12") (pintype "passive"))
      (node (ref "U3") (pin "13") (pinfunction "GND_2_13") (pintype "passive"))
      (node (ref "U4") (pin "2") (pinfunction "A1_2") (pintype "bidirectional"))
      (node (ref "U4") (pin "3") (pinfunction "A2_3") (pintype "bidirectional"))
      (node (ref "U4") (pin "4") (pinfunction "VSS_4") (pintype "power_in"))
      (node (ref "X2") (pin "1") (pinfunction "KL_1") (pintype "passive"))
      (node (ref "X2") (pin "8") (pinfunction "KL_8") (pintype "passive"))
      (node (ref "X3") (pin "1") (pinfunction "SK_1") (pintype "passive"))
      (node (ref "X4") (pin "10") (pinfunction "KL_10") (pintype "passive"))
      (node (ref "X4") (pin "9") (pinfunction "KL_9") (pintype "passive"))
    )
    (net (code "18") (name "IN11") (class "Default")
      (node (ref "U$11") (pin "9") (pinfunction "IN2_9") (pintype "bidirectional"))
      (node (ref "U2") (pin "7") (pinfunction "A5_7") (pintype "output"))
    )
    (net (code "19") (name "IN11_UC") (class "Default")
      (node (ref "U1") (pin "45") (pinfunction "PB8_45") (pintype "bidirectional"))
      (node (ref "U2") (pin "17") (pinfunction "B5_17") (pintype "output"))
    )
    (net (code "20") (name "IN12") (class "Default")
      (node (ref "U$11") (pin "7") (pinfunction "IN1_7") (pintype "bidirectional"))
      (node (ref "U2") (pin "8") (pinfunction "A6_8") (pintype "output"))
    )
    (net (code "21") (name "IN12_UC") (class "Default")
      (node (ref "U1") (pin "46") (pinfunction "PB9_46") (pintype "bidirectional"))
      (node (ref "U2") (pin "16") (pinfunction "B6_16") (pintype "output"))
    )
    (net (code "22") (name "IN21") (class "Default")
      (node (ref "U$11") (pin "15") (pinfunction "IN4_15") (pintype "bidirectional"))
      (node (ref "U2") (pin "9") (pinfunction "A7_9") (pintype "output"))
    )
    (net (code "23") (name "IN21_UC") (class "Default")
      (node (ref "U1") (pin "32") (pinfunction "PA11_32") (pintype "bidirectional"))
      (node (ref "U2") (pin "15") (pinfunction "B7_15") (pintype "output"))
    )
    (net (code "24") (name "IN22") (class "Default")
      (node (ref "U$11") (pin "13") (pinfunction "IN3_13") (pintype "bidirectional"))
      (node (ref "U2") (pin "10") (pinfunction "A8_10") (pintype "output"))
    )
    (net (code "25") (name "IN22_UC") (class "Default")
      (node (ref "U1") (pin "33") (pinfunction "PA12_33") (pintype "bidirectional"))
      (node (ref "U2") (pin "14") (pinfunction "B8_14") (pintype "output"))
    )
    (net (code "26") (name "IN31") (class "Default")
      (node (ref "U$12") (pin "9") (pinfunction "IN2_9") (pintype "bidirectional"))
      (node (ref "U3") (pin "3") (pinfunction "A1_3") (pintype "output"))
    )
    (net (code "27") (name "IN31_UC") (class "Default")
      (node (ref "U1") (pin "25") (pinfunction "PB12_25") (pintype "bidirectional"))
      (node (ref "U3") (pin "21") (pinfunction "B1_21") (pintype "output"))
    )
    (net (code "28") (name "IN32") (class "Default")
      (node (ref "U$12") (pin "7") (pinfunction "IN1_7") (pintype "bidirectional"))
      (node (ref "U3") (pin "4") (pinfunction "A2_4") (pintype "output"))
    )
    (net (code "29") (name "IN32_UC") (class "Default")
      (node (ref "U1") (pin "26") (pinfunction "PB13_26") (pintype "bidirectional"))
      (node (ref "U3") (pin "20") (pinfunction "B2_20") (pintype "output"))
    )
    (net (code "30") (name "IN41") (class "Default")
      (node (ref "U$12") (pin "15") (pinfunction "IN4_15") (pintype "bidirectional"))
      (node (ref "U3") (pin "5") (pinfunction "A3_5") (pintype "output"))
    )
    (net (code "31") (name "IN41_UC") (class "Default")
      (node (ref "U1") (pin "27") (pinfunction "PB14_27") (pintype "bidirectional"))
      (node (ref "U3") (pin "19") (pinfunction "B3_19") (pintype "output"))
    )
    (net (code "32") (name "IN42") (class "Default")
      (node (ref "U$12") (pin "13") (pinfunction "IN3_13") (pintype "bidirectional"))
      (node (ref "U3") (pin "6") (pinfunction "A4_6") (pintype "output"))
    )
    (net (code "33") (name "IN42_UC") (class "Default")
      (node (ref "U1") (pin "28") (pinfunction "PB15_28") (pintype "bidirectional"))
      (node (ref "U3") (pin "18") (pinfunction "B4_18") (pintype "output"))
    )
    (net (code "34") (name "LED") (class "Default")
      (node (ref "U1") (pin "15") (pinfunction "PA5_15") (pintype "bidirectional"))
    )
    (net (code "35") (name "MOT11") (class "Default")
      (node (ref "D2") (pin "A") (pinfunction "A_A") (pintype "passive"))
      (node (ref "D6") (pin "C") (pinfunction "C_C") (pintype "passive"))
      (node (ref "MOTOR_CONNECTOR") (pin "7") (pinfunction "K_7") (pintype "passive"))
      (node (ref "U$11") (pin "5") (pinfunction "OUT2_5") (pintype "bidirectional"))
    )
    (net (code "36") (name "MOT12") (class "Default")
      (node (ref "D3") (pin "A") (pinfunction "A_A") (pintype "passive"))
      (node (ref "D7") (pin "C") (pinfunction "C_C") (pintype "passive"))
      (node (ref "MOTOR_CONNECTOR") (pin "8") (pinfunction "K_8") (pintype "passive"))
      (node (ref "U$11") (pin "4") (pinfunction "OUT1_4") (pintype "bidirectional"))
    )
    (net (code "37") (name "MOT21") (class "Default")
      (node (ref "D4") (pin "A") (pinfunction "A_A") (pintype "passive"))
      (node (ref "D8") (pin "C") (pinfunction "C_C") (pintype "passive"))
      (node (ref "MOTOR_CONNECTOR") (pin "5") (pinfunction "K_5") (pintype "passive"))
      (node (ref "U$11") (pin "17") (pinfunction "OUT4_17") (pintype "bidirectional"))
    )
    (net (code "38") (name "MOT22") (class "Default")
      (node (ref "D5") (pin "A") (pinfunction "A_A") (pintype "passive"))
      (node (ref "D9") (pin "C") (pinfunction "C_C") (pintype "passive"))
      (node (ref "MOTOR_CONNECTOR") (pin "6") (pinfunction "K_6") (pintype "passive"))
      (node (ref "U$11") (pin "16") (pinfunction "OUT3_16") (pintype "bidirectional"))
    )
    (net (code "39") (name "MOT31") (class "Default")
      (node (ref "D10") (pin "A") (pinfunction "A_A") (pintype "passive"))
      (node (ref "D14") (pin "C") (pinfunction "C_C") (pintype "passive"))
      (node (ref "MOTOR_CONNECTOR") (pin "3") (pinfunction "K_3") (pintype "passive"))
      (node (ref "U$12") (pin "5") (pinfunction "OUT2_5") (pintype "bidirectional"))
    )
    (net (code "40") (name "MOT32") (class "Default")
      (node (ref "D11") (pin "A") (pinfunction "A_A") (pintype "passive"))
      (node (ref "D15") (pin "C") (pinfunction "C_C") (pintype "passive"))
      (node (ref "MOTOR_CONNECTOR") (pin "4") (pinfunction "K_4") (pintype "passive"))
      (node (ref "U$12") (pin "4") (pinfunction "OUT1_4") (pintype "bidirectional"))
    )
    (net (code "41") (name "MOT41") (class "Default")
      (node (ref "D12") (pin "A") (pinfunction "A_A") (pintype "passive"))
      (node (ref "D16") (pin "C") (pinfunction "C_C") (pintype "passive"))
      (node (ref "MOTOR_CONNECTOR") (pin "1") (pinfunction "K_1") (pintype "passive"))
      (node (ref "U$12") (pin "17") (pinfunction "OUT4_17") (pintype "bidirectional"))
    )
    (net (code "42") (name "MOT42") (class "Default")
      (node (ref "D13") (pin "A") (pinfunction "A_A") (pintype "passive"))
      (node (ref "D17") (pin "C") (pinfunction "C_C") (pintype "passive"))
      (node (ref "MOTOR_CONNECTOR") (pin "2") (pinfunction "K_2") (pintype "passive"))
      (node (ref "U$12") (pin "16") (pinfunction "OUT3_16") (pintype "bidirectional"))
    )
    (net (code "43") (name "N$8") (class "Default")
      (node (ref "ST-LINK_V2") (pin "6") (pinfunction "6_6") (pintype "passive"))
    )
    (net (code "44") (name "NRST") (class "Default")
      (node (ref "PCB1") (pin "12") (pinfunction "GPIO18_12") (pintype "bidirectional"))
      (node (ref "R1") (pin "1") (pinfunction "1_1") (pintype "passive"))
      (node (ref "ST-LINK_V2") (pin "5") (pinfunction "5_5") (pintype "passive"))
      (node (ref "U1") (pin "7") (pinfunction "NRST_7") (pintype "bidirectional"))
    )
    (net (code "45") (name "Net-(F1-Pad2)") (class "Default")
      (node (ref "F1") (pin "2") (pinfunction "2_2") (pintype "passive"))
      (node (ref "U$3") (pin "OUT1+") (pinfunction "VOUT+_OUT1+") (pintype "output"))
      (node (ref "U$3") (pin "OUT2+") (pinfunction "VOUT+_OUT2+") (pintype "output"))
    )
    (net (code "46") (name "Net-(F2-Pad2)") (class "Default")
      (node (ref "F2") (pin "2") (pinfunction "2_2") (pintype "passive"))
      (node (ref "U$2") (pin "OUT1+") (pinfunction "VOUT+_OUT1+") (pintype "output"))
      (node (ref "U$2") (pin "OUT2+") (pinfunction "VOUT+_OUT2+") (pintype "output"))
    )
    (net (code "47") (name "Net-(F3-Pad1)") (class "Default")
      (node (ref "F3") (pin "1") (pinfunction "1_1") (pintype "passive"))
      (node (ref "U$1") (pin "OUT1+") (pinfunction "VOUT+_OUT1+") (pintype "output"))
      (node (ref "U$1") (pin "OUT2+") (pinfunction "VOUT+_OUT2+") (pintype "output"))
    )
    (net (code "48") (name "Net-(Q1-D)") (class "Default")
      (node (ref "C8") (pin "1") (pinfunction "1_1") (pintype "passive"))
      (node (ref "F1") (pin "1") (pinfunction "1_1") (pintype "passive"))
      (node (ref "Q1") (pin "3") (pinfunction "D_3") (pintype "passive"))
    )
    (net (code "49") (name "Net-(Q1-G)") (class "Default")
      (node (ref "D1") (pin "A") (pinfunction "A_A") (pintype "passive"))
      (node (ref "Q1") (pin "1") (pinfunction "G_1") (pintype "passive"))
      (node (ref "R3") (pin "2") (pinfunction "2_2") (pintype "passive"))
    )
    (net (code "50") (name "Net-(U1A-PF0-OSC_IN)") (class "Default")
      (node (ref "C27") (pin "2") (pinfunction "2_2") (pintype "passive"))
      (node (ref "Q2") (pin "2") (pinfunction "2_2") (pintype "passive"))
      (node (ref "U1") (pin "5") (pinfunction "PF0-OSC_IN_5") (pintype "bidirectional"))
    )
    (net (code "51") (name "Net-(U1A-PF1-OSC_OUT)") (class "Default")
      (node (ref "C28") (pin "2") (pinfunction "2_2") (pintype "passive"))
      (node (ref "Q2") (pin "1") (pinfunction "1_1") (pintype "passive"))
      (node (ref "U1") (pin "6") (pinfunction "PF1-OSC_OUT_6") (pintype "bidirectional"))
    )
    (net (code "52") (name "Net-(U2-DIR)") (class "Default")
      (node (ref "R62") (pin "1") (pinfunction "1_1") (pintype "passive"))
      (node (ref "U2") (pin "2") (pinfunction "DIR_2") (pintype "input"))
      (node (ref "U2") (pin "22") (pinfunction "~{OE}_22") (pintype "input"))
    )
    (net (code "53") (name "Net-(U3-DIR)") (class "Default")
      (node (ref "R63") (pin "1") (pinfunction "1_1") (pintype "passive"))
      (node (ref "U3") (pin "2") (pinfunction "DIR_2") (pintype "input"))
      (node (ref "U3") (pin "22") (pinfunction "~{OE}_22") (pintype "input"))
    )
    (net (code "54") (name "RPI_CLK") (class "Default")
      (node (ref "PCB1") (pin "23") (pinfunction "GPIO11/SCLK_23") (pintype "bidirectional"))
      (node (ref "U1") (pin "39") (pinfunction "PB3_39") (pintype "bidirectional"))
      (node (ref "X2") (pin "7") (pinfunction "KL_7") (pintype "passive"))
    )
    (net (code "55") (name "RPI_MISO") (class "Default")
      (node (ref "PCB1") (pin "21") (pinfunction "GPIO09/MISO_21") (pintype "bidirectional"))
      (node (ref "U1") (pin "40") (pinfunction "PB4_40") (pintype "bidirectional"))
      (node (ref "X2") (pin "5") (pinfunction "KL_5") (pintype "passive"))
    )
    (net (code "56") (name "RPI_MOSI") (class "Default")
      (node (ref "PCB1") (pin "19") (pinfunction "GPIO10/MOSI_19") (pintype "bidirectional"))
      (node (ref "U1") (pin "41") (pinfunction "PB5_41") (pintype "bidirectional"))
      (node (ref "X2") (pin "6") (pinfunction "KL_6") (pintype "passive"))
    )
    (net (code "57") (name "RPI_RXD") (class "Default")
      (node (ref "PCB1") (pin "10") (pinfunction "RXD0/GPIO15_10") (pintype "bidirectional"))
      (node (ref "U1") (pin "42") (pinfunction "PB6_42") (pintype "bidirectional"))
    )
    (net (code "58") (name "RPI_TXD") (class "Default")
      (node (ref "PCB1") (pin "8") (pinfunction "TXD0/GPIO14_8") (pintype "bidirectional"))
      (node (ref "U1") (pin "43") (pinfunction "PB7_43") (pintype "bidirectional"))
    )
    (net (code "59") (name "SCL") (class "Default")
      (node (ref "PCB1") (pin "5") (pinfunction "GPIO03/SCL1_5") (pintype "bidirectional"))
      (node (ref "R60") (pin "1") (pinfunction "1_1") (pintype "passive"))
      (node (ref "U1") (pin "35") (pinfunction "PF6_35") (pintype "bidirectional"))
      (node (ref "U4") (pin "6") (pinfunction "SCL_6") (pintype "bidirectional"))
    )
    (net (code "60") (name "SCL_TX") (class "Default")
      (node (ref "U1") (pin "21") (pinfunction "PB10_21") (pintype "bidirectional"))
      (node (ref "X4") (pin "5") (pinfunction "KL_5") (pintype "passive"))
    )
    (net (code "61") (name "SDA") (class "Default")
      (node (ref "PCB1") (pin "3") (pinfunction "GPIO02/SDA1_3") (pintype "bidirectional"))
      (node (ref "R59") (pin "1") (pinfunction "1_1") (pintype "passive"))
      (node (ref "U1") (pin "36") (pinfunction "PF7_36") (pintype "bidirectional"))
      (node (ref "U4") (pin "5") (pinfunction "SDA_5") (pintype "bidirectional"))
    )
    (net (code "62") (name "SDA_RX") (class "Default")
      (node (ref "U1") (pin "22") (pinfunction "PB11_22") (pintype "bidirectional"))
      (node (ref "X4") (pin "4") (pinfunction "KL_4") (pintype "passive"))
    )
    (net (code "63") (name "SEN1") (class "Default")
      (node (ref "C11") (pin "1") (pinfunction "1_1") (pintype "passive"))
      (node (ref "R6") (pin "1") (pinfunction "1_1") (pintype "passive"))
      (node (ref "U$11") (pin "2") (pinfunction "SENSE_A_2") (pintype "bidirectional"))
      (node (ref "U1") (pin "10") (pinfunction "PA0_10") (pintype "bidirectional"))
    )
    (net (code "64") (name "SEN2") (class "Default")
      (node (ref "C12") (pin "1") (pinfunction "1_1") (pintype "passive"))
      (node (ref "R5") (pin "1") (pinfunction "1_1") (pintype "passive"))
      (node (ref "U$11") (pin "19") (pinfunction "SENSE_B_19") (pintype "bidirectional"))
      (node (ref "U1") (pin "11") (pinfunction "PA1_11") (pintype "bidirectional"))
    )
    (net (code "65") (name "SEN3") (class "Default")
      (node (ref "C13") (pin "1") (pinfunction "1_1") (pintype "passive"))
      (node (ref "R8") (pin "1") (pinfunction "1_1") (pintype "passive"))
      (node (ref "U$12") (pin "2") (pinfunction "SENSE_A_2") (pintype "bidirectional"))
      (node (ref "U1") (pin "12") (pinfunction "PA2_12") (pintype "bidirectional"))
    )
    (net (code "66") (name "SEN4") (class "Default")
      (node (ref "C14") (pin "1") (pinfunction "1_1") (pintype "passive"))
      (node (ref "R7") (pin "1") (pinfunction "1_1") (pintype "passive"))
      (node (ref "U$12") (pin "19") (pinfunction "SENSE_B_19") (pintype "bidirectional"))
      (node (ref "U1") (pin "13") (pinfunction "PA3_13") (pintype "bidirectional"))
    )
    (net (code "67") (name "SERVO1") (class "Default")
      (node (ref "U3") (pin "7") (pinfunction "A5_7") (pintype "output"))
      (node (ref "X4") (pin "6") (pinfunction "KL_6") (pintype "passive"))
    )
    (net (code "68") (name "SERVO1_UC") (class "Default")
      (node (ref "U1") (pin "29") (pinfunction "PA8_29") (pintype "bidirectional"))
      (node (ref "U3") (pin "17") (pinfunction "B5_17") (pintype "output"))
    )
    (net (code "69") (name "SERVO2") (class "Default")
      (node (ref "U3") (pin "8") (pinfunction "A6_8") (pintype "output"))
      (node (ref "X4") (pin "7") (pinfunction "KL_7") (pintype "passive"))
    )
    (net (code "70") (name "SERVO2_UC") (class "Default")
      (node (ref "U1") (pin "30") (pinfunction "PA9_30") (pintype "bidirectional"))
      (node (ref "U3") (pin "16") (pinfunction "B6_16") (pintype "output"))
    )
    (net (code "71") (name "SERVO3") (class "Default")
      (node (ref "U3") (pin "9") (pinfunction "A7_9") (pintype "output"))
      (node (ref "X4") (pin "8") (pinfunction "KL_8") (pintype "passive"))
    )
    (net (code "72") (name "SERVO3_UC") (class "Default")
      (node (ref "U1") (pin "31") (pinfunction "PA10_31") (pintype "bidirectional"))
      (node (ref "U3") (pin "15") (pinfunction "B7_15") (pintype "output"))
    )
    (net (code "73") (name "SPI1_NSS") (class "Default")
      (node (ref "PCB1") (pin "24") (pinfunction "~{CE0}/GPIO08_24") (pintype "bidirectional"))
      (node (ref "R61") (pin "1") (pinfunction "1_1") (pintype "passive"))
      (node (ref "U1") (pin "38") (pinfunction "PA15_38") (pintype "bidirectional"))
    )
    (net (code "74") (name "SWCLK") (class "Default")
      (node (ref "PCB1") (pin "22") (pinfunction "GEN6/GPIO25_22") (pintype "bidirectional"))
      (node (ref "ST-LINK_V2") (pin "1") (pinfunction "1_1") (pintype "passive"))
      (node (ref "U1") (pin "37") (pinfunction "PA14-SWCLK_37") (pintype "bidirectional"))
    )
    (net (code "75") (name "SWDIO") (class "Default")
      (node (ref "PCB1") (pin "18") (pinfunction "GEN5/GPIO24_18") (pintype "bidirectional"))
      (node (ref "ST-LINK_V2") (pin "2") (pinfunction "2_2") (pintype "passive"))
      (node (ref "U1") (pin "34") (pinfunction "PA13-SWDIO_34") (pintype "bidirectional"))
    )
    (net (code "76") (name "VCC") (class "Default")
      (node (ref "C5") (pin "+") (pinfunction "+_+") (pintype "passive"))
      (node (ref "D10") (pin "C") (pinfunction "C_C") (pintype "passive"))
      (node (ref "D11") (pin "C") (pinfunction "C_C") (pintype "passive"))
      (node (ref "D12") (pin "C") (pinfunction "C_C") (pintype "passive"))
      (node (ref "D13") (pin "C") (pinfunction "C_C") (pintype "passive"))
      (node (ref "D2") (pin "C") (pinfunction "C_C") (pintype "passive"))
      (node (ref "D3") (pin "C") (pinfunction "C_C") (pintype "passive"))
      (node (ref "D4") (pin "C") (pinfunction "C_C") (pintype "passive"))
      (node (ref "D5") (pin "C") (pinfunction "C_C") (pintype "passive"))
      (node (ref "R45") (pin "2") (pinfunction "2_2") (pintype "passive"))
      (node (ref "U$1") (pin "IN1+") (pinfunction "VIN+_IN1+") (pintype "input"))
      (node (ref "U$1") (pin "IN2+") (pinfunction "VIN+_IN2+") (pintype "input"))
      (node (ref "U$11") (pin "6") (pinfunction "VS_6") (pintype "bidirectional"))
      (node (ref "U$12") (pin "6") (pinfunction "VS_6") (pintype "bidirectional"))
      (node (ref "U$2") (pin "IN1+") (pinfunction "VIN+_IN1+") (pintype "input"))
      (node (ref "U$2") (pin "IN2+") (pinfunction "VIN+_IN2+") (pintype "input"))
      (node (ref "U$3") (pin "IN1+") (pinfunction "VIN+_IN1+") (pintype "input"))
      (node (ref "U$3") (pin "IN2+") (pinfunction "VIN+_IN2+") (pintype "input"))
      (node (ref "X3") (pin "2") (pinfunction "SK_2") (pintype "passive"))
    )
    (net (code "77") (name "unconnected-(PCB1-BL-PadPE_BL)") (class "Default")
      (node (ref "PCB1") (pin "PE_BL") (pinfunction "BL_PE_BL") (pintype "bidirectional"))
    )
    (net (code "78") (name "unconnected-(PCB1-BR-PadPE_BR)") (class "Default")
      (node (ref "PCB1") (pin "PE_BR") (pinfunction "BR_PE_BR") (pintype "bidirectional"))
    )
    (net (code "79") (name "unconnected-(PCB1-GEN4{slash}GPIO23-Pad16)") (class "Default")
      (node (ref "PCB1") (pin "16") (pinfunction "GEN4/GPIO23_16") (pintype "bidirectional"))
    )
    (net (code "80") (name "unconnected-(PCB1-GPIO04{slash}GCKL-Pad7)") (class "Default")
      (node (ref "PCB1") (pin "7") (pinfunction "GPIO04/GCKL_7") (pintype "bidirectional"))
    )
    (net (code "81") (name "unconnected-(PCB1-GPIO05-Pad29)") (class "Default")
      (node (ref "PCB1") (pin "29") (pinfunction "GPIO05_29") (pintype "bidirectional"))
    )
    (net (code "82") (name "unconnected-(PCB1-GPIO06-Pad31)") (class "Default")
      (node (ref "PCB1") (pin "31") (pinfunction "GPIO06_31") (pintype "bidirectional"))
    )
    (net (code "83") (name "unconnected-(PCB1-GPIO12-Pad32)") (class "Default")
      (node (ref "PCB1") (pin "32") (pinfunction "GPIO12_32") (pintype "bidirectional"))
    )
    (net (code "84") (name "unconnected-(PCB1-GPIO13-Pad33)") (class "Default")
      (node (ref "PCB1") (pin "33") (pinfunction "GPIO13_33") (pintype "bidirectional"))
    )
    (net (code "85") (name "unconnected-(PCB1-GPIO16-Pad36)") (class "Default")
      (node (ref "PCB1") (pin "36") (pinfunction "GPIO16_36") (pintype "bidirectional"))
    )
    (net (code "86") (name "unconnected-(PCB1-GPIO17{slash}GEN0-Pad11)") (class "Default")
      (node (ref "PCB1") (pin "11") (pinfunction "GPIO17/GEN0_11") (pintype "bidirectional"))
    )
    (net (code "87") (name "unconnected-(PCB1-GPIO19-Pad35)") (class "Default")
      (node (ref "PCB1") (pin "35") (pinfunction "GPIO19_35") (pintype "bidirectional"))
    )
    (net (code "88") (name "unconnected-(PCB1-GPIO20-Pad38)") (class "Default")
      (node (ref "PCB1") (pin "38") (pinfunction "GPIO20_38") (pintype "bidirectional"))
    )
    (net (code "89") (name "unconnected-(PCB1-GPIO21-Pad40)") (class "Default")
      (node (ref "PCB1") (pin "40") (pinfunction "GPIO21_40") (pintype "bidirectional"))
    )
    (net (code "90") (name "unconnected-(PCB1-GPIO22{slash}GEN3-Pad15)") (class "Default")
      (node (ref "PCB1") (pin "15") (pinfunction "GPIO22/GEN3_15") (pintype "bidirectional"))
    )
    (net (code "91") (name "unconnected-(PCB1-GPIO26-Pad37)") (class "Default")
      (node (ref "PCB1") (pin "37") (pinfunction "GPIO26_37") (pintype "bidirectional"))
    )
    (net (code "92") (name "unconnected-(PCB1-GPIO27{slash}GEN2-Pad13)") (class "Default")
      (node (ref "PCB1") (pin "13") (pinfunction "GPIO27/GEN2_13") (pintype "bidirectional"))
    )
    (net (code "93") (name "unconnected-(PCB1-ID_SC-Pad28)") (class "Default")
      (node (ref "PCB1") (pin "28") (pinfunction "ID_SC_28") (pintype "bidirectional"))
    )
    (net (code "94") (name "unconnected-(PCB1-ID_SD-Pad27)") (class "Default")
      (node (ref "PCB1") (pin "27") (pinfunction "ID_SD_27") (pintype "bidirectional"))
    )
    (net (code "95") (name "unconnected-(PCB1-TL-PadPE_TL)") (class "Default")
      (node (ref "PCB1") (pin "PE_TL") (pinfunction "TL_PE_TL") (pintype "bidirectional"))
    )
    (net (code "96") (name "unconnected-(PCB1-TR-PadPE_TR)") (class "Default")
      (node (ref "PCB1") (pin "PE_TR") (pinfunction "TR_PE_TR") (pintype "bidirectional"))
    )
    (net (code "97") (name "unconnected-(PCB1-~{CE}{slash}GPIO07-Pad26)") (class "Default")
      (node (ref "PCB1") (pin "26") (pinfunction "~{CE}/GPIO07_26") (pintype "bidirectional"))
    )
    (net (code "98") (name "unconnected-(U$11-NC-Pad3)") (class "Default")
      (node (ref "U$11") (pin "3") (pinfunction "NC_3") (pintype "bidirectional"))
    )
    (net (code "99") (name "unconnected-(U$11-NC-Pad18)") (class "Default")
      (node (ref "U$11") (pin "18") (pinfunction "NC_18") (pintype "bidirectional"))
    )
    (net (code "100") (name "unconnected-(U$12-NC-Pad3)") (class "Default")
      (node (ref "U$12") (pin "3") (pinfunction "NC_3") (pintype "bidirectional"))
    )
    (net (code "101") (name "unconnected-(U$12-NC-Pad18)") (class "Default")
      (node (ref "U$12") (pin "18") (pinfunction "NC_18") (pintype "bidirectional"))
    )
    (net (code "102") (name "unconnected-(U1A-PF14-OSC32_IN-Pad3)") (class "Default")
      (node (ref "U1") (pin "3") (pinfunction "PF14-OSC32_IN_3") (pintype "bidirectional"))
    )
    (net (code "103") (name "unconnected-(U1A-PF15-OSC32_OUT-Pad4)") (class "Default")
      (node (ref "U1") (pin "4") (pinfunction "PF15-OSC32_OUT_4") (pintype "bidirectional"))
    )
    (net (code "104") (name "unconnected-(U1B-PC13-Pad2)") (class "Default")
      (node (ref "U1") (pin "2") (pinfunction "PC13_2") (pintype "bidirectional"))
    )
    (net (code "105") (name "unconnected-(U1C-PB2-Pad20)") (class "Default")
      (node (ref "U1") (pin "20") (pinfunction "PB2_20") (pintype "bidirectional"))
    )
    (net (code "106") (name "unconnected-(U3-A8-Pad10)") (class "Default")
      (node (ref "U3") (pin "10") (pinfunction "A8_10") (pintype "output"))
    )
    (net (code "107") (name "unconnected-(U3-B8-Pad14)") (class "Default")
      (node (ref "U3") (pin "14") (pinfunction "B8_14") (pintype "output"))
    )
    (net (code "108") (name "unconnected-(U4-A0-Pad1)") (class "Default")
      (node (ref "U4") (pin "1") (pinfunction "A0_1") (pintype "bidirectional"))
    )
  )
)
